# TiLDA_Mk2_Prototype_v0_1.net
KiCad netlist of a schematic drawn in EAGLE
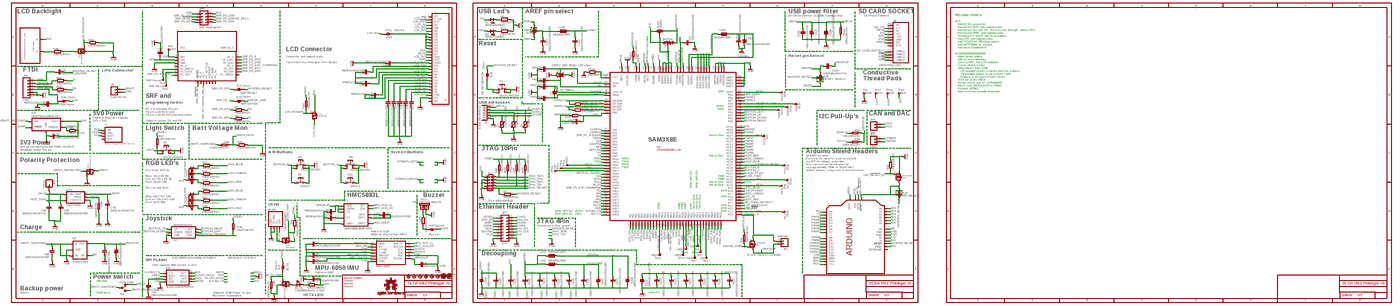
[diagram p0: schematic, sheet 1, overview]
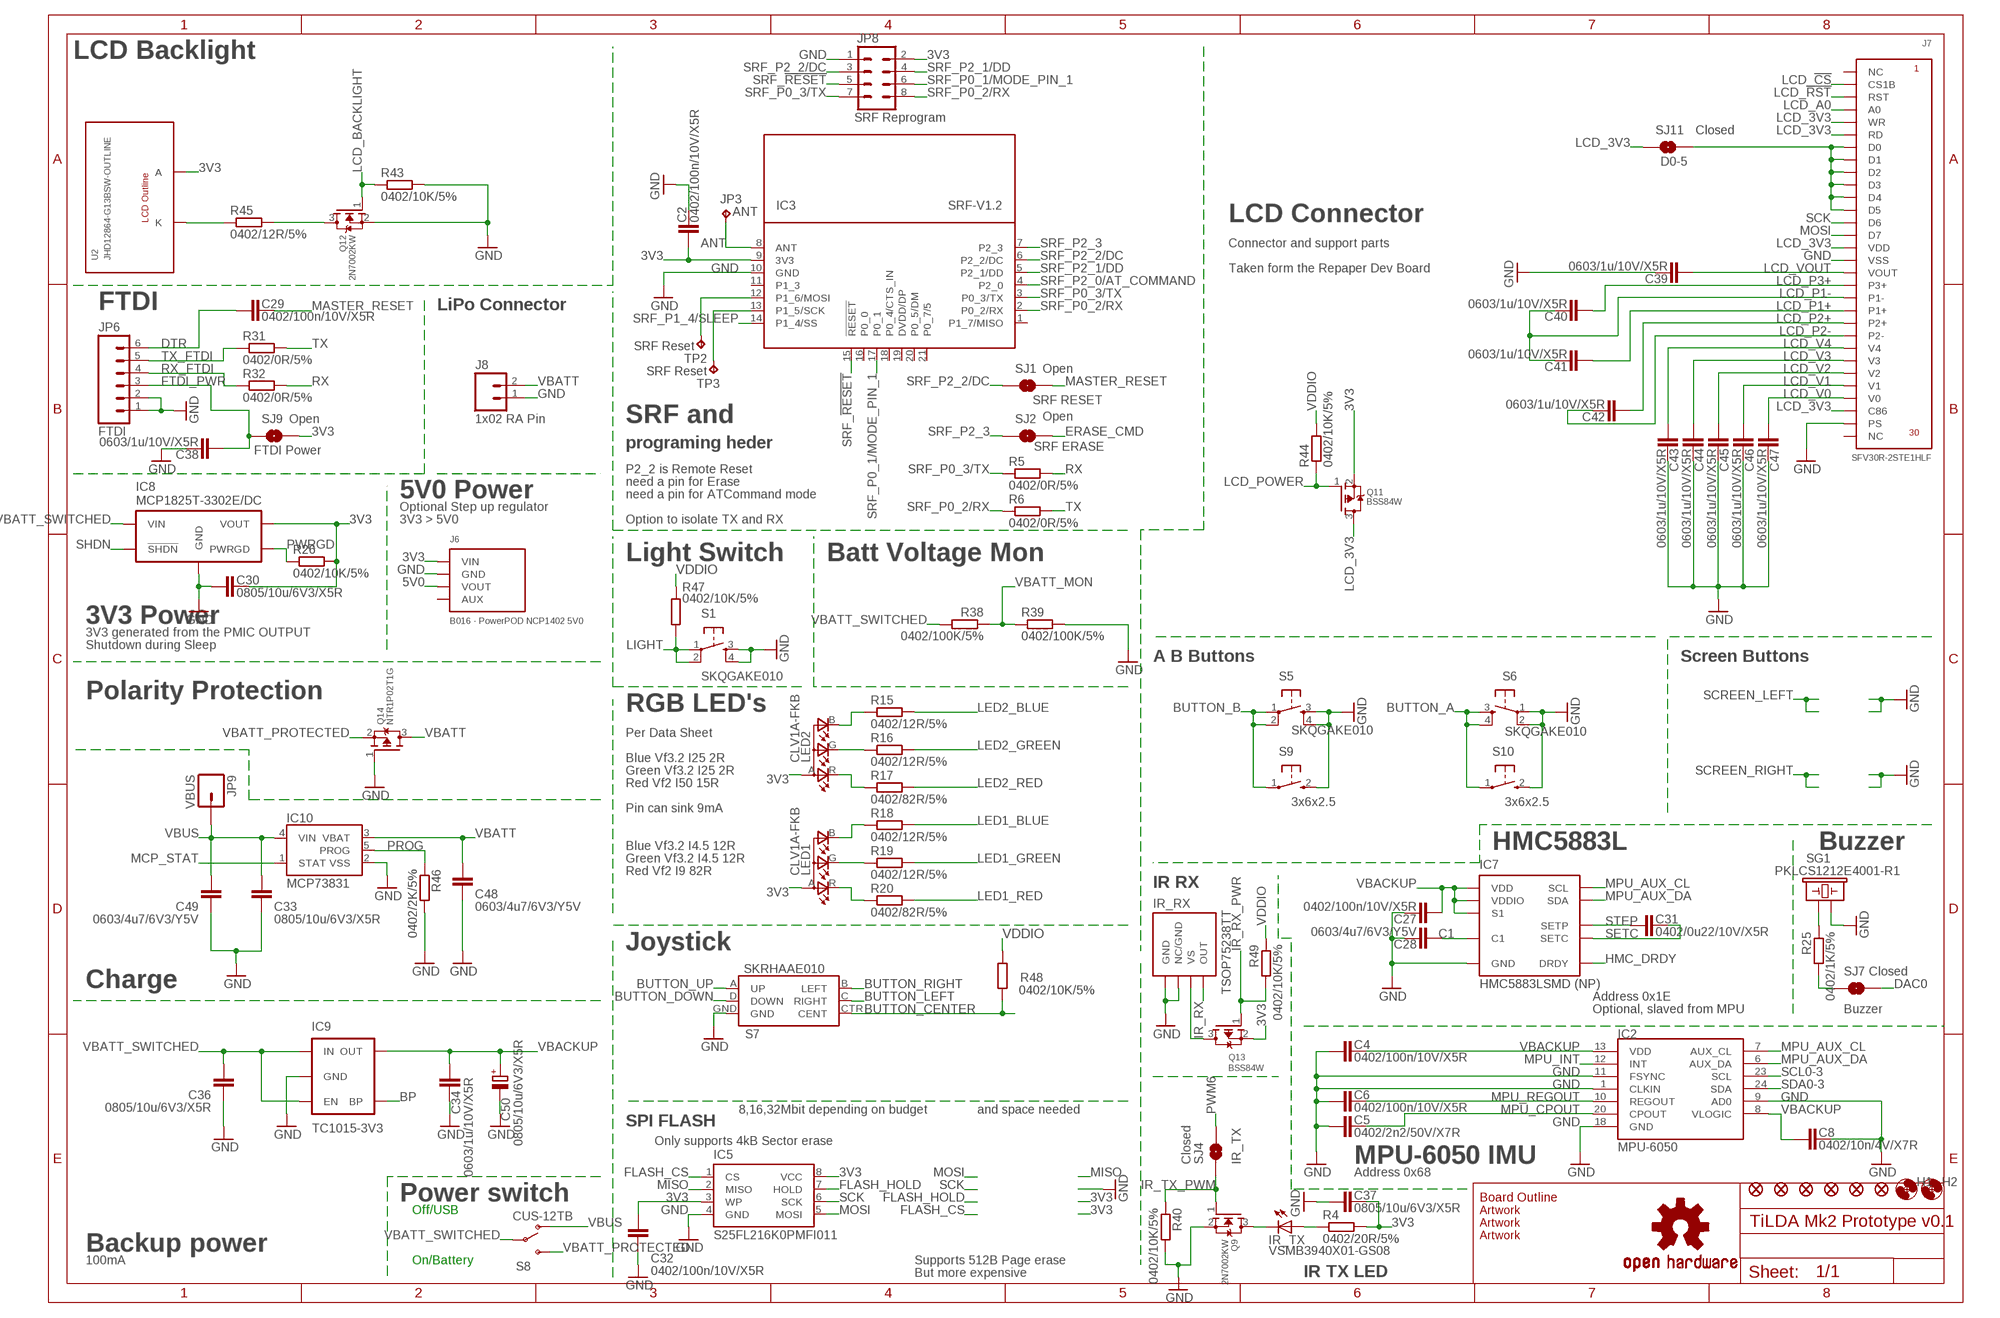
[diagram p1: schematic, sheet 1, part 1 of 4]
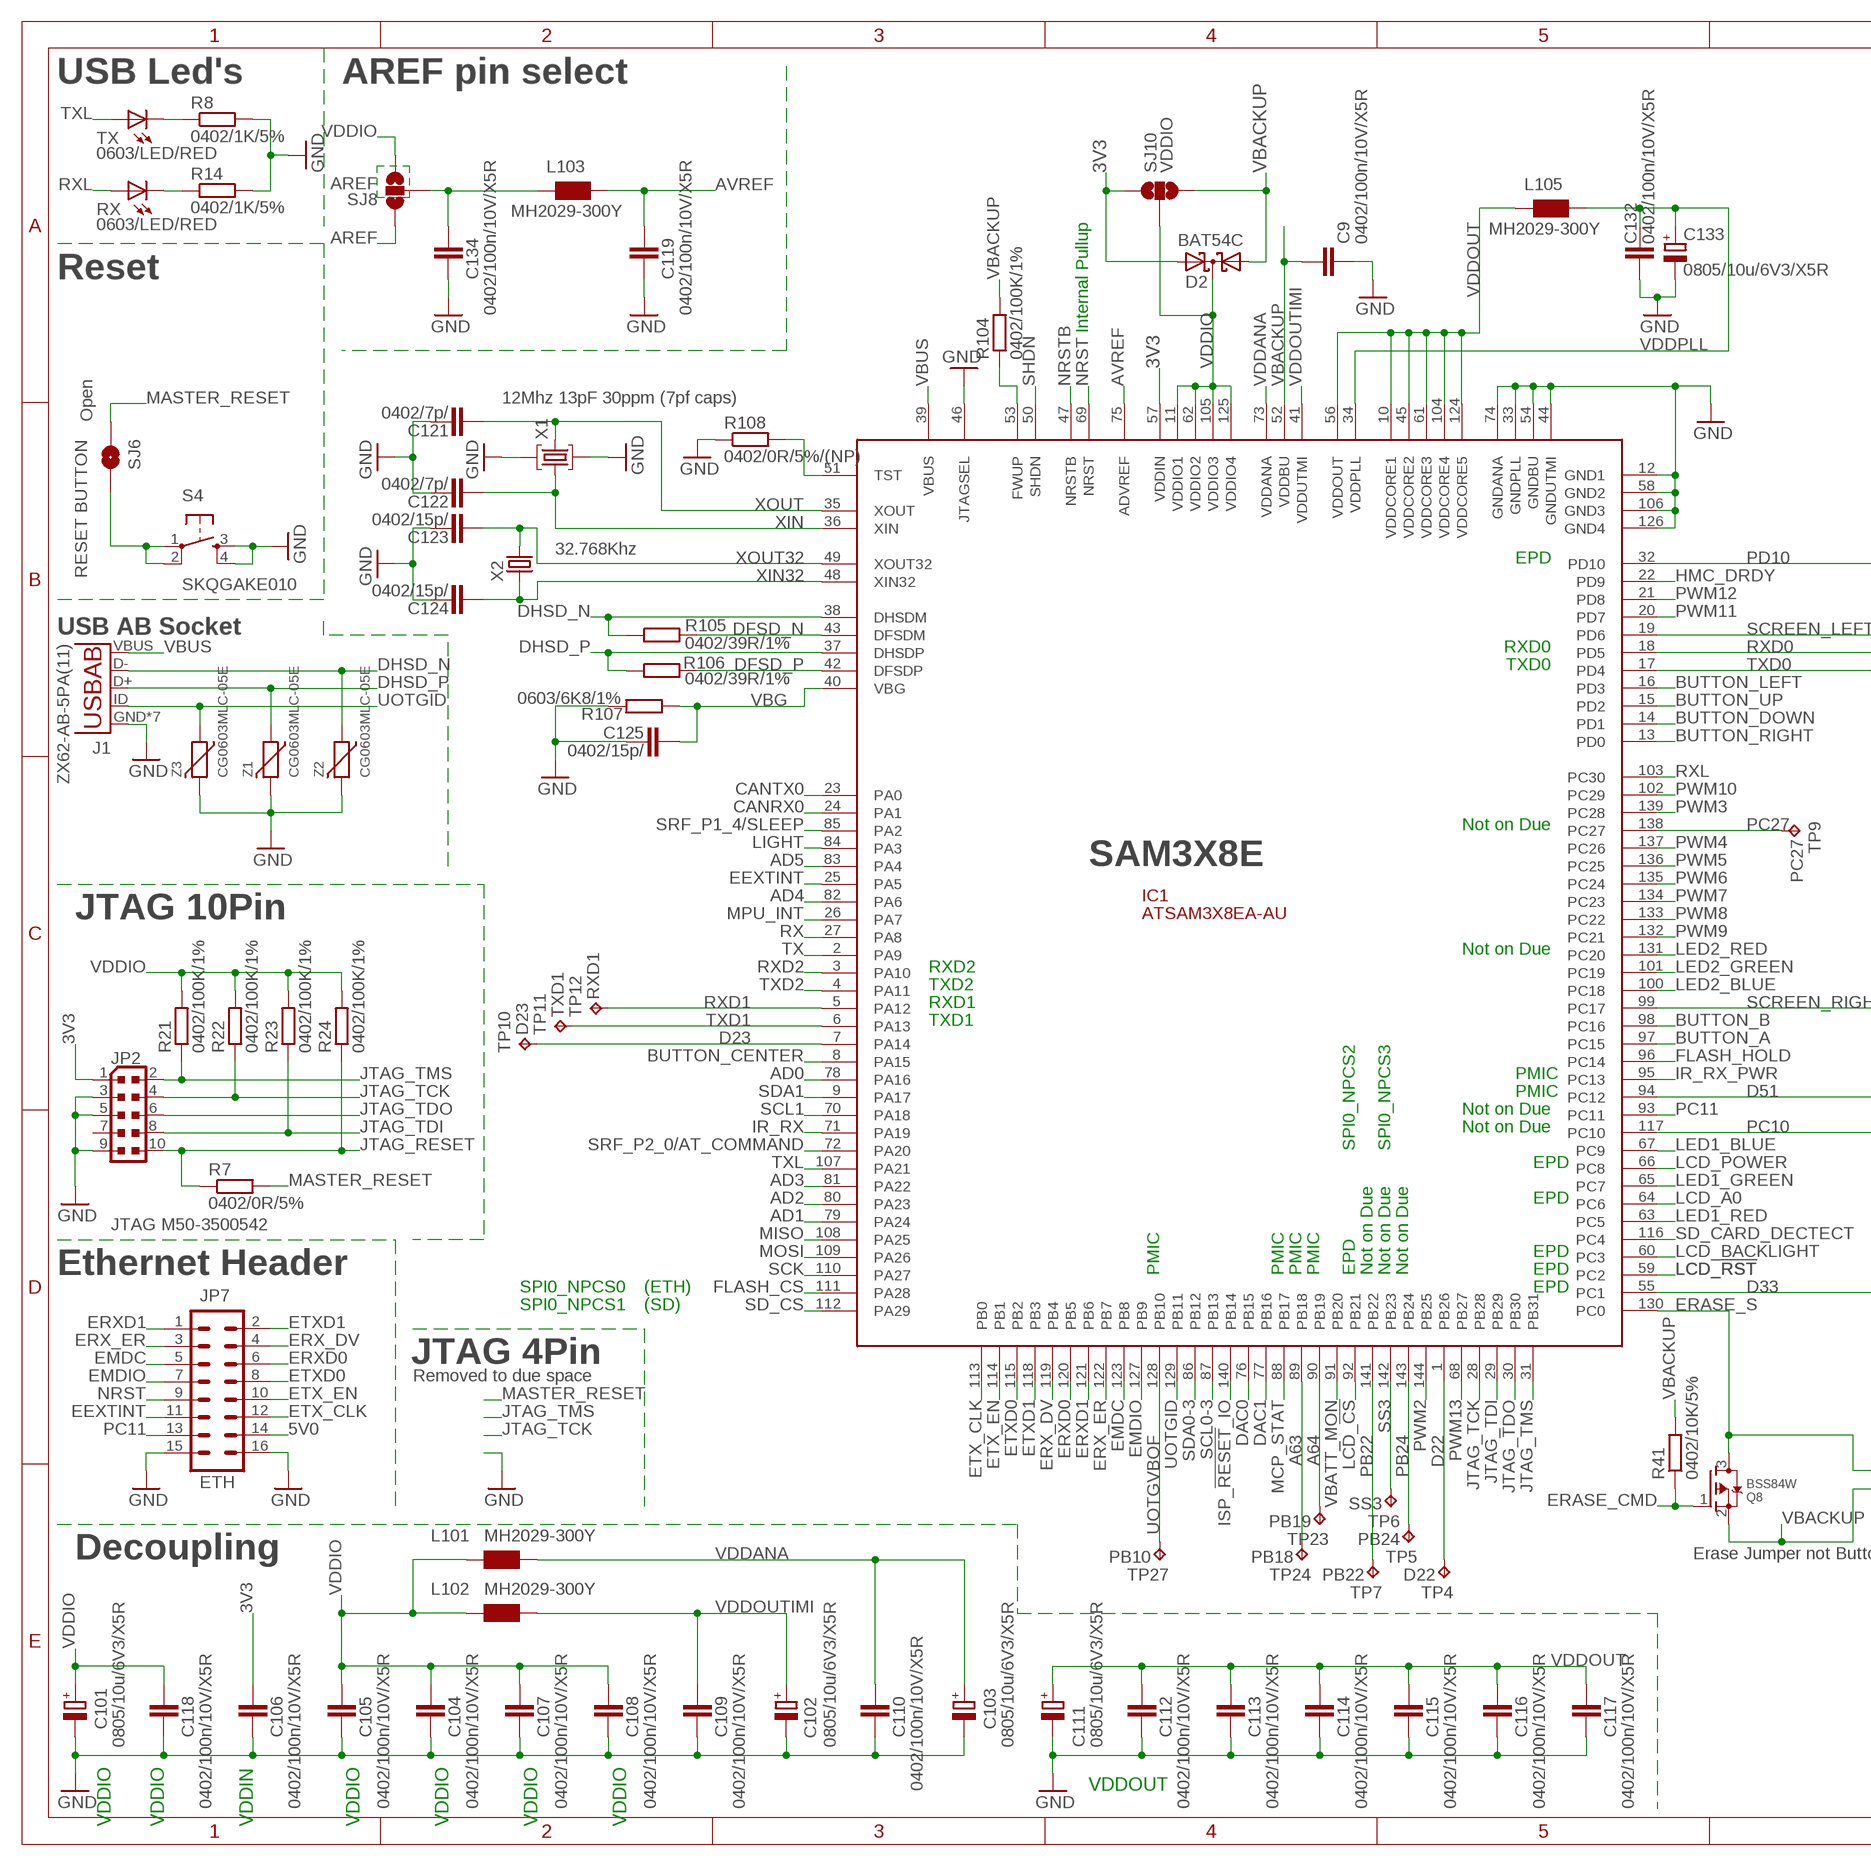
[diagram p2: schematic, sheet 1, part 2 of 4]
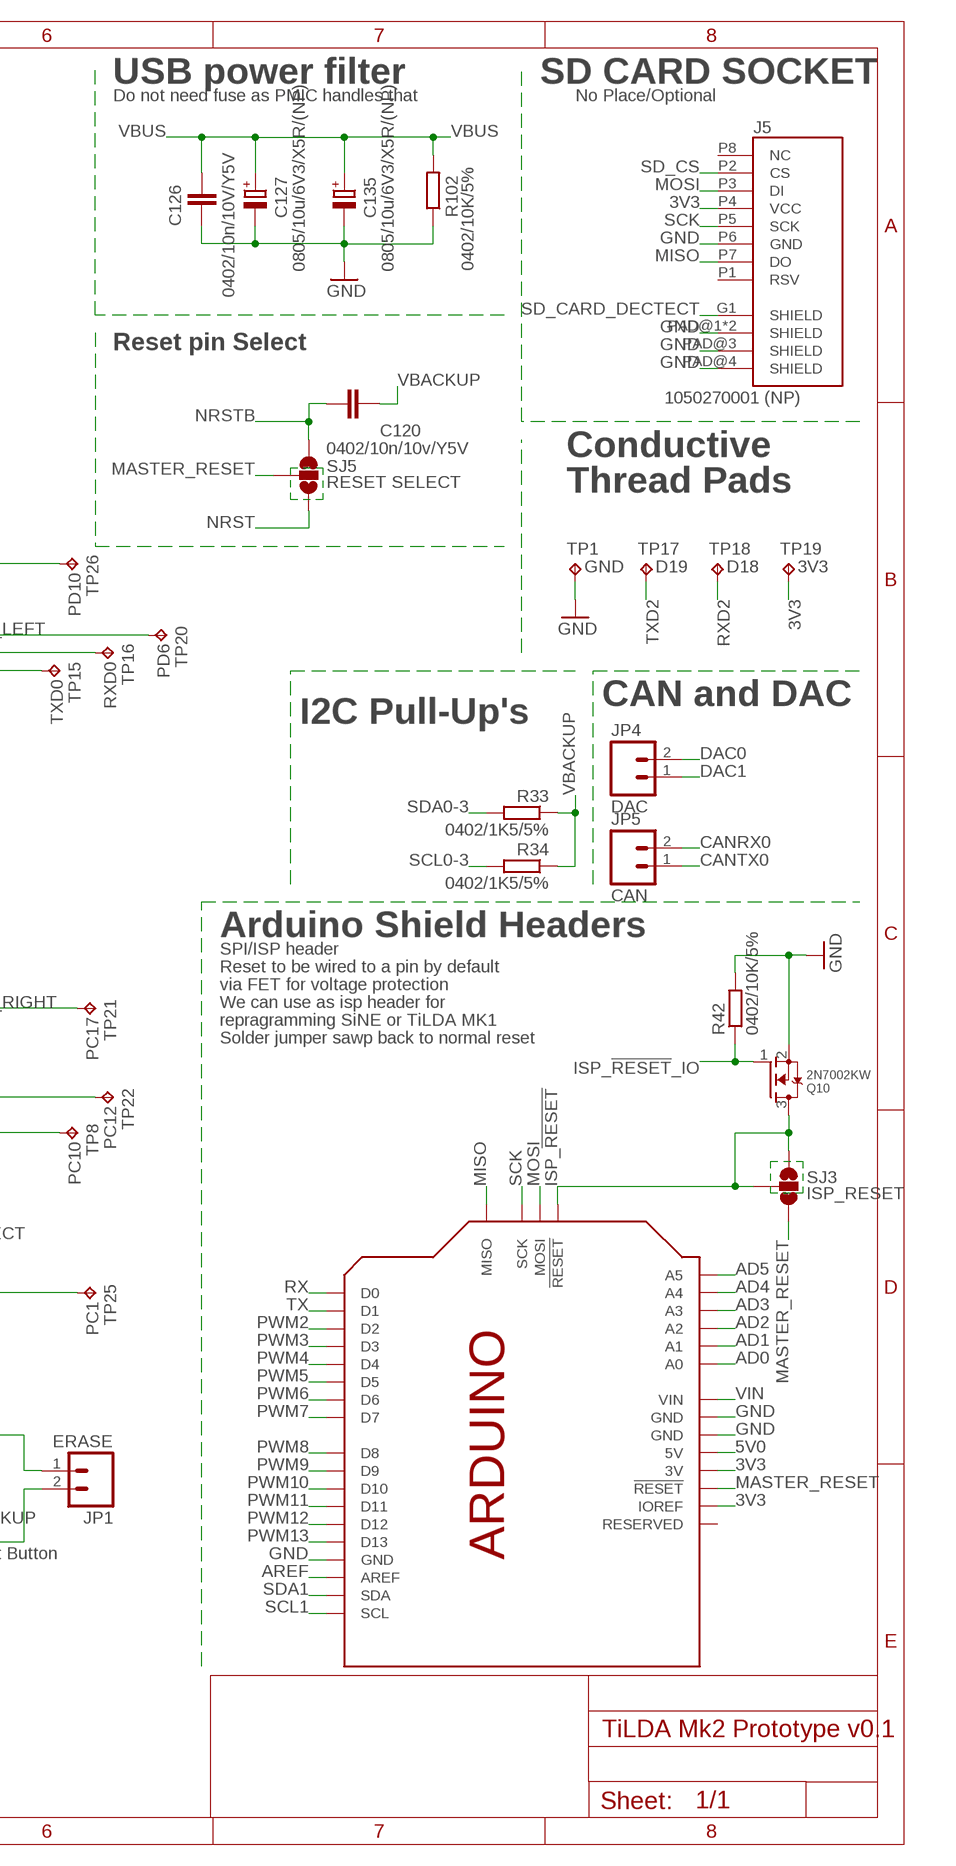
[diagram p3: schematic, sheet 1, part 3 of 4]
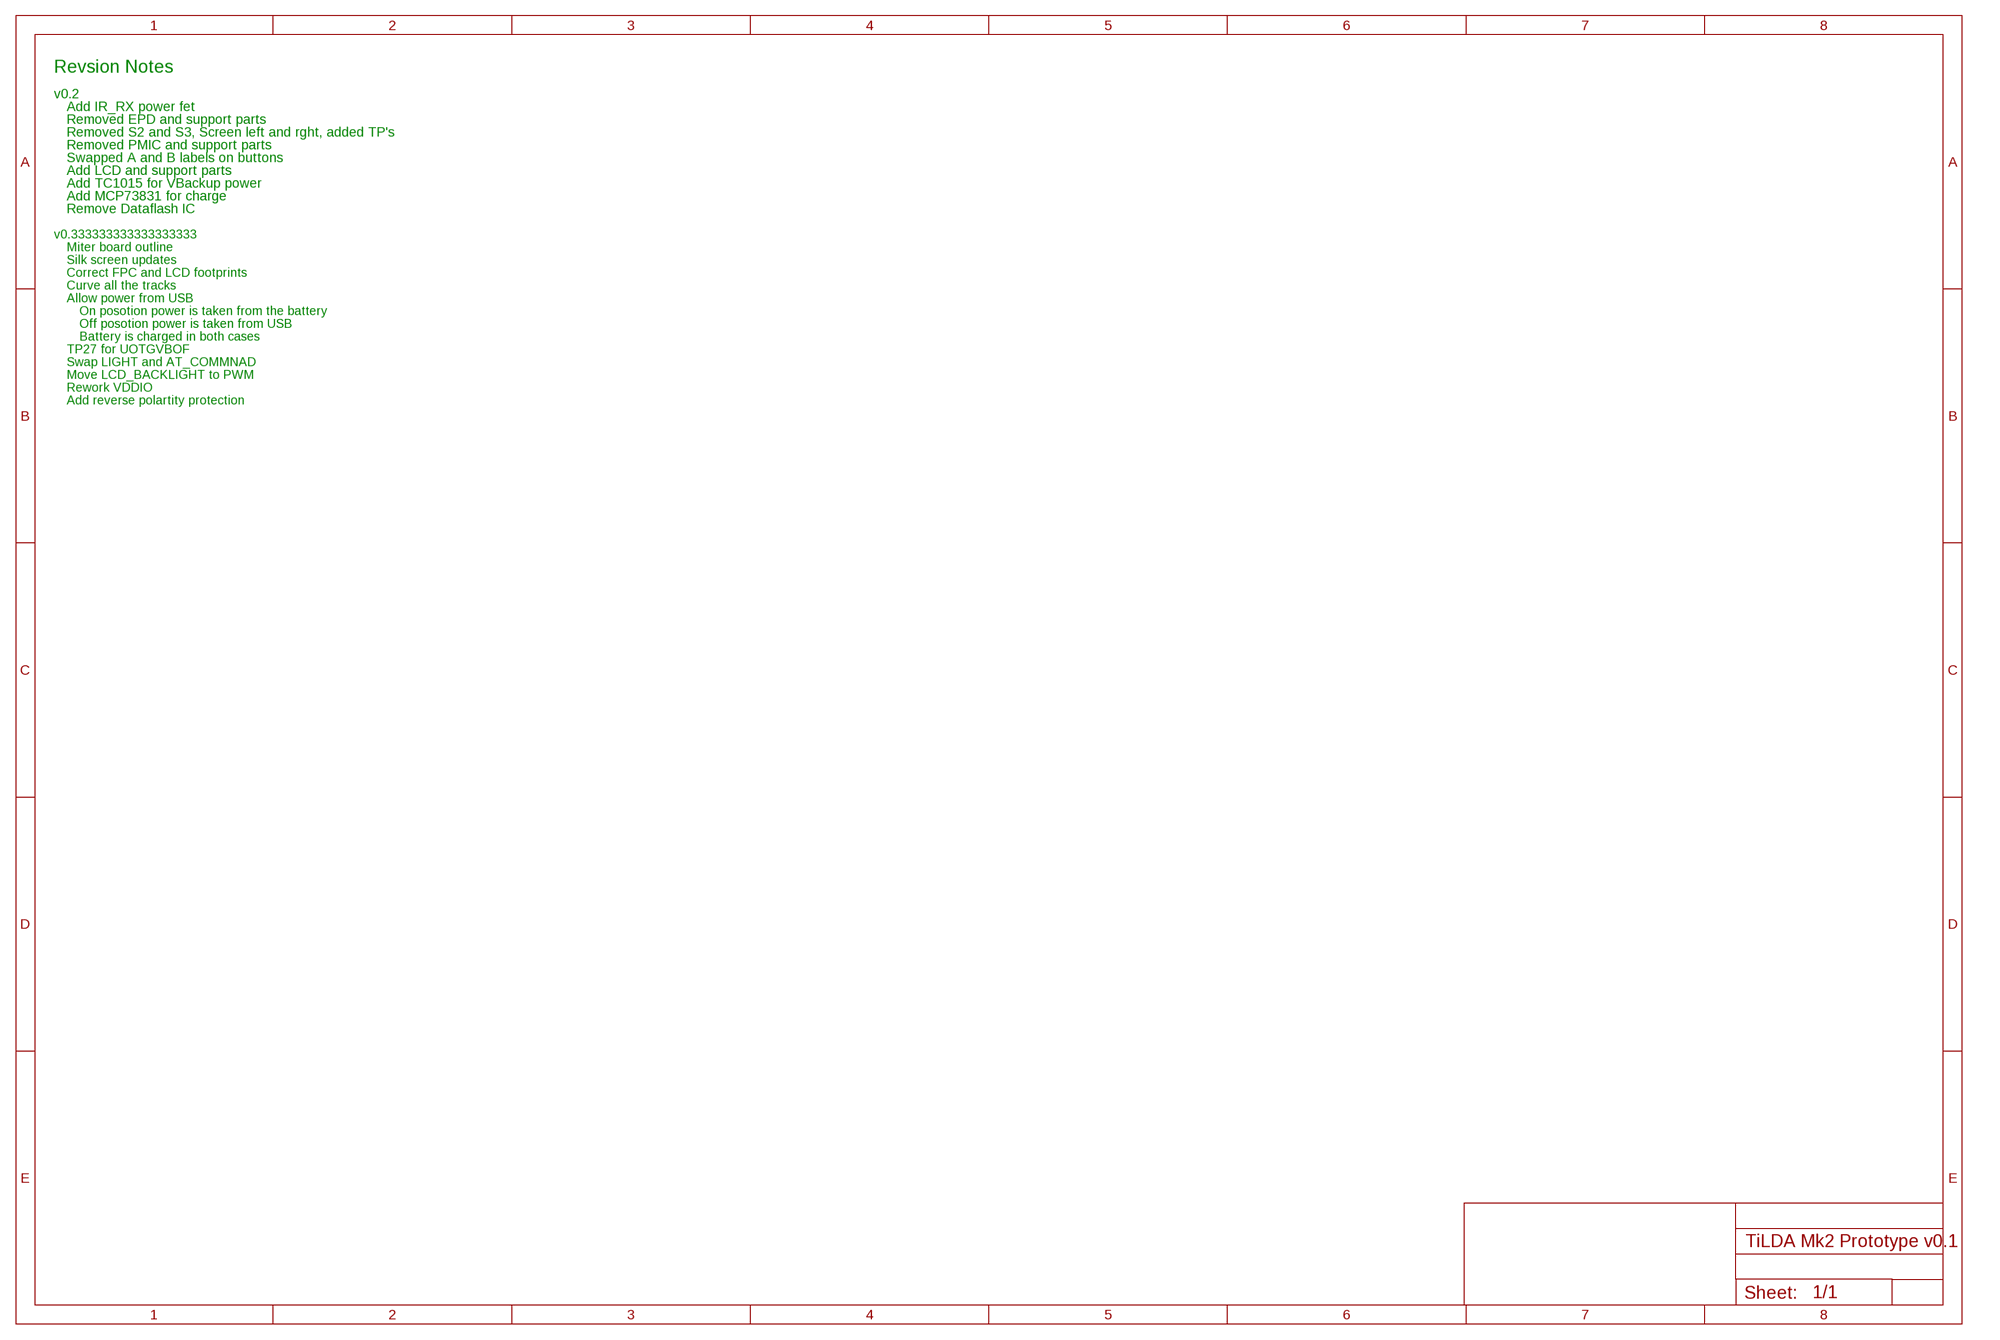
[diagram p4: schematic, sheet 1, part 4 of 4]

(export (version "E")
  (design (tool "Eeschema 10.0.6"))
  (components
    (comp (ref "ARTWORK1")
      (value "ARTWORK_FRONT1")
      (footprint "eagle-import:TILDA_ARTWORK_FRONT1")
      (libsource (lib "eagle-import") (part "ARTWORK_FRONT1"))
    )
    (comp (ref "ARTWORK2")
      (value "ARTWORK_ACHIEVEMENT2")
      (footprint "eagle-import:TILDA_ARTWORK_ACHIEVEMENT2")
      (libsource (lib "eagle-import") (part "ARTWORK_ACHIEVEMENT2"))
    )
    (comp (ref "ARTWORK3")
      (value "ARTWORK_ACHIEVEMENT3")
      (footprint "eagle-import:TILDA_ARTWORK_ACHIEVEMENT3")
      (libsource (lib "eagle-import") (part "ARTWORK_ACHIEVEMENT3"))
    )
    (comp (ref "C2")
      (value "0402/100n/10V/X5R")
      (footprint "eagle-import:C0402-ARDUINO-ROUND")
      (libsource (lib "eagle-import") (part "C-EUC0402-ARDUINO-ROUND"))
    )
    (comp (ref "C4")
      (value "0402/100n/10V/X5R")
      (footprint "eagle-import:C0402-ARDUINO-ROUND")
      (libsource (lib "eagle-import") (part "C-EUC0402-ARDUINO-ROUND"))
    )
    (comp (ref "C5")
      (value "0402/2n2/50V/X7R")
      (footprint "eagle-import:C0402-ARDUINO-ROUND")
      (libsource (lib "eagle-import") (part "C-EUC0402-ARDUINO-ROUND"))
    )
    (comp (ref "C6")
      (value "0402/100n/10V/X5R")
      (footprint "eagle-import:C0402-ARDUINO-ROUND")
      (libsource (lib "eagle-import") (part "C-EUC0402-ARDUINO-ROUND"))
    )
    (comp (ref "C8")
      (value "0402/10n/4V/X7R")
      (footprint "eagle-import:C0402-ARDUINO-ROUND")
      (libsource (lib "eagle-import") (part "C-EUC0402-ARDUINO-ROUND"))
    )
    (comp (ref "C9")
      (value "0402/100n/10V/X5R")
      (footprint "eagle-import:C0402-ARDUINO-ROUND")
      (libsource (lib "eagle-import") (part "C-EUC0402-ARDUINO-ROUND"))
    )
    (comp (ref "C27")
      (value "0402/100n/10V/X5R")
      (footprint "eagle-import:C0402-ARDUINO-ROUND")
      (libsource (lib "eagle-import") (part "C-EUC0402-ARDUINO-ROUND"))
    )
    (comp (ref "C28")
      (value "0603/4u7/6V3/Y5V")
      (footprint "eagle-import:C0603-ROUND")
      (libsource (lib "eagle-import") (part "C-EUC0603-ROUND"))
    )
    (comp (ref "C29")
      (value "0402/100n/10V/X5R")
      (footprint "eagle-import:C0402-ARDUINO-ROUND")
      (libsource (lib "eagle-import") (part "C-EUC0402-ARDUINO-ROUND"))
    )
    (comp (ref "C30")
      (value "0805/10u/6V3/X5R")
      (footprint "eagle-import:C0805RND")
      (libsource (lib "eagle-import") (part "C-EUC0805RND"))
    )
    (comp (ref "C31")
      (value "0402/0u22/10V/X5R")
      (footprint "eagle-import:C0402-ARDUINO-ROUND")
      (libsource (lib "eagle-import") (part "C-EUC0402-ARDUINO-ROUND"))
    )
    (comp (ref "C32")
      (value "0402/100n/10V/X5R")
      (footprint "eagle-import:C0402-ARDUINO-ROUND")
      (libsource (lib "eagle-import") (part "C-EUC0402-ARDUINO-ROUND"))
    )
    (comp (ref "C33")
      (value "0805/10u/6V3/X5R")
      (footprint "eagle-import:C0805RND")
      (libsource (lib "eagle-import") (part "C-EUC0805RND"))
    )
    (comp (ref "C34")
      (value "0603/1u/10V/X5R")
      (footprint "eagle-import:C0603-ROUND")
      (libsource (lib "eagle-import") (part "C-EUC0603-ROUND"))
    )
    (comp (ref "C36")
      (value "0805/10u/6V3/X5R")
      (footprint "eagle-import:C0805RND")
      (libsource (lib "eagle-import") (part "C-EUC0805RND"))
    )
    (comp (ref "C37")
      (value "0805/10u/6V3/X5R")
      (footprint "eagle-import:C0805RND")
      (libsource (lib "eagle-import") (part "C-EUC0805RND"))
    )
    (comp (ref "C38")
      (value "0603/1u/10V/X5R")
      (footprint "eagle-import:C0603-ROUND")
      (libsource (lib "eagle-import") (part "C-EUC0603-ROUND"))
    )
    (comp (ref "C39")
      (value "0603/1u/10V/X5R")
      (footprint "eagle-import:C0603-ROUND")
      (libsource (lib "eagle-import") (part "C-EUC0603-ROUND"))
    )
    (comp (ref "C40")
      (value "0603/1u/10V/X5R")
      (footprint "eagle-import:C0603-ROUND")
      (libsource (lib "eagle-import") (part "C-EUC0603-ROUND"))
    )
    (comp (ref "C41")
      (value "0603/1u/10V/X5R")
      (footprint "eagle-import:C0603-ROUND")
      (libsource (lib "eagle-import") (part "C-EUC0603-ROUND"))
    )
    (comp (ref "C42")
      (value "0603/1u/10V/X5R")
      (footprint "eagle-import:C0603-ROUND")
      (libsource (lib "eagle-import") (part "C-EUC0603-ROUND"))
    )
    (comp (ref "C43")
      (value "0603/1u/10V/X5R")
      (footprint "eagle-import:C0603-ROUND")
      (libsource (lib "eagle-import") (part "C-EUC0603-ROUND"))
    )
    (comp (ref "C44")
      (value "0603/1u/10V/X5R")
      (footprint "eagle-import:C0603-ROUND")
      (libsource (lib "eagle-import") (part "C-EUC0603-ROUND"))
    )
    (comp (ref "C45")
      (value "0603/1u/10V/X5R")
      (footprint "eagle-import:C0603-ROUND")
      (libsource (lib "eagle-import") (part "C-EUC0603-ROUND"))
    )
    (comp (ref "C46")
      (value "0603/1u/10V/X5R")
      (footprint "eagle-import:C0603-ROUND")
      (libsource (lib "eagle-import") (part "C-EUC0603-ROUND"))
    )
    (comp (ref "C47")
      (value "0603/1u/10V/X5R")
      (footprint "eagle-import:C0603-ROUND")
      (libsource (lib "eagle-import") (part "C-EUC0603-ROUND"))
    )
    (comp (ref "C48")
      (value "0603/4u7/6V3/Y5V")
      (footprint "eagle-import:C0603-ROUND")
      (libsource (lib "eagle-import") (part "C-EUC0603-ROUND"))
    )
    (comp (ref "C49")
      (value "0603/4u7/6V3/Y5V")
      (footprint "eagle-import:C0603-ROUND")
      (libsource (lib "eagle-import") (part "C-EUC0603-ROUND"))
    )
    (comp (ref "C50")
      (value "0805/10u/6V3/X5R")
      (footprint "eagle-import:C0805RNDPOL")
      (libsource (lib "eagle-import") (part "CPOL-EU-C0805RNDPOL"))
    )
    (comp (ref "C101")
      (value "0805/10u/6V3/X5R")
      (footprint "eagle-import:C0805RNDPOL")
      (libsource (lib "eagle-import") (part "CPOL-EU-C0805RNDPOL"))
    )
    (comp (ref "C102")
      (value "0805/10u/6V3/X5R")
      (footprint "eagle-import:C0805RNDPOL")
      (libsource (lib "eagle-import") (part "CPOL-EU-C0805RNDPOL"))
    )
    (comp (ref "C103")
      (value "0805/10u/6V3/X5R")
      (footprint "eagle-import:C0805RNDPOL")
      (libsource (lib "eagle-import") (part "CPOL-EU-C0805RNDPOL"))
    )
    (comp (ref "C104")
      (value "0402/100n/10V/X5R")
      (footprint "eagle-import:C0402-ARDUINO-ROUND")
      (libsource (lib "eagle-import") (part "C-EUC0402-ARDUINO-ROUND"))
    )
    (comp (ref "C105")
      (value "0402/100n/10V/X5R")
      (footprint "eagle-import:C0402-ARDUINO-ROUND")
      (libsource (lib "eagle-import") (part "C-EUC0402-ARDUINO-ROUND"))
    )
    (comp (ref "C106")
      (value "0402/100n/10V/X5R")
      (footprint "eagle-import:C0402-ARDUINO-ROUND")
      (libsource (lib "eagle-import") (part "C-EUC0402-ARDUINO-ROUND"))
    )
    (comp (ref "C107")
      (value "0402/100n/10V/X5R")
      (footprint "eagle-import:C0402-ARDUINO-ROUND")
      (libsource (lib "eagle-import") (part "C-EUC0402-ARDUINO-ROUND"))
    )
    (comp (ref "C108")
      (value "0402/100n/10V/X5R")
      (footprint "eagle-import:C0402-ARDUINO-ROUND")
      (libsource (lib "eagle-import") (part "C-EUC0402-ARDUINO-ROUND"))
    )
    (comp (ref "C109")
      (value "0402/100n/10V/X5R")
      (footprint "eagle-import:C0402-ARDUINO-ROUND")
      (libsource (lib "eagle-import") (part "C-EUC0402-ARDUINO-ROUND"))
    )
    (comp (ref "C110")
      (value "0402/100n/10V/X5R")
      (footprint "eagle-import:C0402-ARDUINO-ROUND")
      (libsource (lib "eagle-import") (part "C-EUC0402-ARDUINO-ROUND"))
    )
    (comp (ref "C111")
      (value "0805/10u/6V3/X5R")
      (footprint "eagle-import:C0805RNDPOL")
      (libsource (lib "eagle-import") (part "CPOL-EU-C0805RNDPOL"))
    )
    (comp (ref "C112")
      (value "0402/100n/10V/X5R")
      (footprint "eagle-import:C0402-ARDUINO-ROUND")
      (libsource (lib "eagle-import") (part "C-EUC0402-ARDUINO-ROUND"))
    )
    (comp (ref "C113")
      (value "0402/100n/10V/X5R")
      (footprint "eagle-import:C0402-ARDUINO-ROUND")
      (libsource (lib "eagle-import") (part "C-EUC0402-ARDUINO-ROUND"))
    )
    (comp (ref "C114")
      (value "0402/100n/10V/X5R")
      (footprint "eagle-import:C0402-ARDUINO-ROUND")
      (libsource (lib "eagle-import") (part "C-EUC0402-ARDUINO-ROUND"))
    )
    (comp (ref "C115")
      (value "0402/100n/10V/X5R")
      (footprint "eagle-import:C0402-ARDUINO-ROUND")
      (libsource (lib "eagle-import") (part "C-EUC0402-ARDUINO-ROUND"))
    )
    (comp (ref "C116")
      (value "0402/100n/10V/X5R")
      (footprint "eagle-import:C0402-ARDUINO-ROUND")
      (libsource (lib "eagle-import") (part "C-EUC0402-ARDUINO-ROUND"))
    )
    (comp (ref "C117")
      (value "0402/100n/10V/X5R")
      (footprint "eagle-import:C0402-ARDUINO-ROUND")
      (libsource (lib "eagle-import") (part "C-EUC0402-ARDUINO-ROUND"))
    )
    (comp (ref "C118")
      (value "0402/100n/10V/X5R")
      (footprint "eagle-import:C0402-ARDUINO-ROUND")
      (libsource (lib "eagle-import") (part "C-EUC0402-ARDUINO-ROUND"))
    )
    (comp (ref "C119")
      (value "0402/100n/10V/X5R")
      (footprint "eagle-import:C0402-ARDUINO-ROUND")
      (libsource (lib "eagle-import") (part "C-EUC0402-ARDUINO-ROUND"))
    )
    (comp (ref "C120")
      (value "0402/10n/10v/Y5V")
      (footprint "eagle-import:C0402-ARDUINO-ROUND")
      (libsource (lib "eagle-import") (part "C-EUC0402-ARDUINO-ROUND"))
    )
    (comp (ref "C121")
      (value "0402/7p/")
      (footprint "eagle-import:C0402-ARDUINO-ROUND")
      (libsource (lib "eagle-import") (part "C-EUC0402-ARDUINO-ROUND"))
    )
    (comp (ref "C122")
      (value "0402/7p/")
      (footprint "eagle-import:C0402-ARDUINO-ROUND")
      (libsource (lib "eagle-import") (part "C-EUC0402-ARDUINO-ROUND"))
    )
    (comp (ref "C123")
      (value "0402/15p/")
      (footprint "eagle-import:C0402-ARDUINO-ROUND")
      (libsource (lib "eagle-import") (part "C-EUC0402-ARDUINO-ROUND"))
    )
    (comp (ref "C124")
      (value "0402/15p/")
      (footprint "eagle-import:C0402-ARDUINO-ROUND")
      (libsource (lib "eagle-import") (part "C-EUC0402-ARDUINO-ROUND"))
    )
    (comp (ref "C125")
      (value "0402/15p/")
      (footprint "eagle-import:C0402-ARDUINO-ROUND")
      (libsource (lib "eagle-import") (part "C-EUC0402-ARDUINO-ROUND"))
    )
    (comp (ref "C126")
      (value "0402/10n/10V/Y5V")
      (footprint "eagle-import:C0402-ARDUINO-ROUND")
      (libsource (lib "eagle-import") (part "C-EUC0402-ARDUINO-ROUND"))
    )
    (comp (ref "C127")
      (value "0805/10u/6V3/X5R/(NP)")
      (footprint "eagle-import:C0805RNDPOL")
      (libsource (lib "eagle-import") (part "CPOL-EU-C0805RNDPOL"))
    )
    (comp (ref "C132")
      (value "0402/100n/10V/X5R")
      (footprint "eagle-import:C0402-ARDUINO-ROUND")
      (libsource (lib "eagle-import") (part "C-EUC0402-ARDUINO-ROUND"))
    )
    (comp (ref "C133")
      (value "0805/10u/6V3/X5R")
      (footprint "eagle-import:C0805RNDPOL")
      (libsource (lib "eagle-import") (part "CPOL-EU-C0805RNDPOL"))
    )
    (comp (ref "C134")
      (value "0402/100n/10V/X5R")
      (footprint "eagle-import:C0402-ARDUINO-ROUND")
      (libsource (lib "eagle-import") (part "C-EUC0402-ARDUINO-ROUND"))
    )
    (comp (ref "C135")
      (value "0805/10u/6V3/X5R/(NP)")
      (footprint "eagle-import:C0805RNDPOL")
      (libsource (lib "eagle-import") (part "CPOL-EU-C0805RNDPOL"))
    )
    (comp (ref "D2")
      (value "BAT54C")
      (footprint "eagle-import:SOT23")
      (libsource (lib "eagle-import") (part "BAT54C"))
    )
    (comp (ref "FID1")
      (value "FIDUCIAL1X2.5-STOP")
      (footprint "eagle-import:FIDUCIAL-1X2.5-STOP")
      (libsource (lib "eagle-import") (part "FIDUCIAL1X2.5-STOP"))
    )
    (comp (ref "FID2")
      (value "FIDUCIAL1X2.5-STOP")
      (footprint "eagle-import:FIDUCIAL-1X2.5-STOP")
      (libsource (lib "eagle-import") (part "FIDUCIAL1X2.5-STOP"))
    )
    (comp (ref "FID3")
      (value "FIDUCIAL1X2.5-STOP")
      (footprint "eagle-import:FIDUCIAL-1X2.5-STOP")
      (libsource (lib "eagle-import") (part "FIDUCIAL1X2.5-STOP"))
    )
    (comp (ref "FID4")
      (value "FIDUCIAL1X2.5-STOP")
      (footprint "eagle-import:FIDUCIAL-1X2.5-STOP")
      (libsource (lib "eagle-import") (part "FIDUCIAL1X2.5-STOP"))
    )
    (comp (ref "FID5")
      (value "FIDUCIAL1X2.5-STOP")
      (footprint "eagle-import:FIDUCIAL-1X2.5-STOP")
      (libsource (lib "eagle-import") (part "FIDUCIAL1X2.5-STOP"))
    )
    (comp (ref "FID6")
      (value "FIDUCIAL1X2.5-STOP")
      (footprint "eagle-import:FIDUCIAL-1X2.5-STOP")
      (libsource (lib "eagle-import") (part "FIDUCIAL1X2.5-STOP"))
    )
    (comp (ref "H1")
      (value "MOUNT-HOLE4.5-LWK")
      (footprint "eagle-import:4,5-LWK")
      (libsource (lib "eagle-import") (part "MOUNT-HOLE4.5-LWK"))
    )
    (comp (ref "H2")
      (value "MOUNT-HOLE4.5-LWK")
      (footprint "eagle-import:4,5-LWK")
      (libsource (lib "eagle-import") (part "MOUNT-HOLE4.5-LWK"))
    )
    (comp (ref "IC1")
      (value "ATSAM3X8EA-AU")
      (footprint "eagle-import:LQFP144")
      (libsource (lib "eagle-import") (part "ATSAM3X/AAU"))
    )
    (comp (ref "IC2")
      (value "MPU-6050")
      (footprint "eagle-import:QFN-24-NODIE")
      (libsource (lib "eagle-import") (part "MPU-6050"))
    )
    (comp (ref "IC3")
      (value "SRF-V1.2")
      (footprint "eagle-import:SRF-LANDING-1.2")
      (libsource (lib "eagle-import") (part "SRF-LANDING-1.2"))
    )
    (comp (ref "IC5")
      (value "S25FL216K0PMFI011")
      (footprint "eagle-import:SO08-EIAJ")
      (libsource (lib "eagle-import") (part "SPI_FLASH-X25XXSMD1"))
    )
    (comp (ref "IC7")
      (value "HMC5883LSMD (NP)")
      (footprint "eagle-import:16LPCC")
      (libsource (lib "eagle-import") (part "HMC5883LSMD"))
    )
    (comp (ref "IC8")
      (value "MCP1825T-3302E/DC")
      (footprint "eagle-import:SOT127P700X180-6N")
      (libsource (lib "eagle-import") (part "MCP1825T-3302E/DC"))
    )
    (comp (ref "IC9")
      (value "TC1015-3V3")
      (footprint "eagle-import:SOT23-5")
      (libsource (lib "eagle-import") (part "V_REG_LDOSMD"))
    )
    (comp (ref "IC10")
      (value "MCP73831")
      (footprint "eagle-import:SOT23-5")
      (libsource (lib "eagle-import") (part "MCP73831"))
    )
    (comp (ref "IR_RX")
      (value "TSOP75238TT")
      (footprint "eagle-import:TSOP75X")
      (libsource (lib "eagle-import") (part "IR-RECEIVERTSOP75438TT"))
    )
    (comp (ref "IR_TX")
      (value "VSMB3940X01-GS08")
      (footprint "eagle-import:P-LCC-2")
      (libsource (lib "eagle-import") (part "IR-SENDER-PLCC"))
    )
    (comp (ref "J1")
      (value "ZX62-AB-5PA(11)")
      (footprint "eagle-import:USB-AB-MICRO-SMD_LWK")
      (libsource (lib "eagle-import") (part "USB-AB-LWK"))
    )
    (comp (ref "J3")
      (value "Arduino Headers")
      (footprint "eagle-import:ARDUINOR3-LWKTXT-REF-SPI")
      (libsource (lib "eagle-import") (part "ARDUINOSPI-REFRENCE"))
    )
    (comp (ref "J5")
      (value "1050270001 (NP)")
      (footprint "eagle-import:105027-LWK")
      (libsource (lib "eagle-import") (part "USD-SOCKET-105027-LWK"))
    )
    (comp (ref "J6")
      (value "B016 - PowerPOD NCP1402 5V0")
      (footprint "eagle-import:POWER-POD-EMF")
      (libsource (lib "eagle-import") (part "POWER-POD-EMF"))
    )
    (comp (ref "J7")
      (value "SFV30R-2STE1HLF")
      (footprint "eagle-import:SFV30R-2STE1HLF")
      (libsource (lib "eagle-import") (part "JHD12863-G13BSW-CONNECTOR-SFV30R-2STE1HLF"))
    )
    (comp (ref "J8")
      (value "1x02 RA Pin")
      (footprint "eagle-import:1X02_RA")
      (libsource (lib "eagle-import") (part "M02RA"))
    )
    (comp (ref "JP1")
      (value "ERASE")
      (footprint "eagle-import:1X02")
      (libsource (lib "eagle-import") (part "M02PTH"))
    )
    (comp (ref "JP2")
      (value "JTAG M50-3500542")
      (footprint "eagle-import:PINHEAD_2X05_127")
      (libsource (lib "eagle-import") (part "PINHEAD_PINHD-2X5PASSO127"))
    )
    (comp (ref "JP3")
      (value "ANT")
      (footprint "eagle-import:P1-13")
      (libsource (lib "eagle-import") (part "TPPAD1-13"))
    )
    (comp (ref "JP4")
      (value "DAC")
      (footprint "eagle-import:1X02_NO_SILK_OCT")
      (libsource (lib "eagle-import") (part "M021X02_NO_SILK_OCT"))
    )
    (comp (ref "JP5")
      (value "CAN")
      (footprint "eagle-import:1X02_NO_SILK_OCT")
      (libsource (lib "eagle-import") (part "M021X02_NO_SILK_OCT"))
    )
    (comp (ref "JP6")
      (value "FTDI")
      (footprint "eagle-import:1X06")
      (libsource (lib "eagle-import") (part "M06SIP"))
    )
    (comp (ref "JP7")
      (value "ETH")
      (footprint "eagle-import:2X8")
      (libsource (lib "eagle-import") (part "M08X2"))
    )
    (comp (ref "JP8")
      (value "SRF Reprogram")
      (footprint "eagle-import:2X4-PAD")
      (libsource (lib "eagle-import") (part "M04X2-PAD"))
    )
    (comp (ref "JP9")
      (value "VBUS")
      (footprint "eagle-import:1X01")
      (libsource (lib "eagle-import") (part "M01PTH"))
    )
    (comp (ref "L101")
      (value "MH2029-300Y")
      (footprint "eagle-import:WUERTH-0805")
      (libsource (lib "eagle-import") (part "WE-CBF_0805"))
    )
    (comp (ref "L102")
      (value "MH2029-300Y")
      (footprint "eagle-import:WUERTH-0805")
      (libsource (lib "eagle-import") (part "WE-CBF_0805"))
    )
    (comp (ref "L103")
      (value "MH2029-300Y")
      (footprint "eagle-import:WUERTH-0805")
      (libsource (lib "eagle-import") (part "WE-CBF_0805"))
    )
    (comp (ref "L105")
      (value "MH2029-300Y")
      (footprint "eagle-import:WUERTH-0805")
      (libsource (lib "eagle-import") (part "WE-CBF_0805"))
    )
    (comp (ref "LED1")
      (value "CLV1A-FKB")
      (footprint "eagle-import:LED-RGB_CLV1A-FKB")
      (libsource (lib "eagle-import") (part "LED-RGB_CLV1A-FKB"))
    )
    (comp (ref "LED2")
      (value "CLV1A-FKB")
      (footprint "eagle-import:LED-RGB_CLV1A-FKB")
      (libsource (lib "eagle-import") (part "LED-RGB_CLV1A-FKB"))
    )
    (comp (ref "LOGO1")
      (value "OSHW-LOGOM")
      (footprint "eagle-import:OSHW-LOGO-M")
      (libsource (lib "eagle-import") (part "OSHW-LOGOM"))
    )
    (comp (ref "OUTLINE1")
      (value "TILDA_BOARDOUTLINE-MITER")
      (footprint "eagle-import:TILDA_BADGEBOARDBARE-VERYWIDE-MITER")
      (libsource (lib "eagle-import") (part "TILDA_BOARDOUTLINE-MITER"))
    )
    (comp (ref "Q8")
      (value "BSS84W")
      (footprint "eagle-import:SC70-3-R")
      (libsource (lib "eagle-import") (part "MOSFET-P-SC70-3"))
    )
    (comp (ref "Q9")
      (value "2N7002KW")
      (footprint "eagle-import:SC70-3-R")
      (libsource (lib "eagle-import") (part "MOSFET-NSC70-3"))
    )
    (comp (ref "Q10")
      (value "2N7002KW")
      (footprint "eagle-import:SC70-3-R")
      (libsource (lib "eagle-import") (part "MOSFET-NSC70-3"))
    )
    (comp (ref "Q11")
      (value "BSS84W")
      (footprint "eagle-import:SC70-3-R")
      (libsource (lib "eagle-import") (part "MOSFET-P-SC70-3"))
    )
    (comp (ref "Q12")
      (value "2N7002KW")
      (footprint "eagle-import:SC70-3-R")
      (libsource (lib "eagle-import") (part "MOSFET-NSC70-3"))
    )
    (comp (ref "Q13")
      (value "BSS84W")
      (footprint "eagle-import:SC70-3-R")
      (libsource (lib "eagle-import") (part "MOSFET-P-SC70-3"))
    )
    (comp (ref "Q14")
      (value "NTR1P02T1G")
      (footprint "eagle-import:SOT23-R")
      (libsource (lib "eagle-import") (part "MOSFET-P-SOT23"))
    )
    (comp (ref "R4")
      (value "0402/20R/5%")
      (footprint "eagle-import:R0402-ARDUINO-ROUND")
      (libsource (lib "eagle-import") (part "R-EU_R0402-ARDUINO-ROUND"))
    )
    (comp (ref "R5")
      (value "0402/0R/5%")
      (footprint "eagle-import:R0402-ARDUINO-ROUND")
      (libsource (lib "eagle-import") (part "R-EU_R0402-ARDUINO-ROUND"))
    )
    (comp (ref "R6")
      (value "0402/0R/5%")
      (footprint "eagle-import:R0402-ARDUINO-ROUND")
      (libsource (lib "eagle-import") (part "R-EU_R0402-ARDUINO-ROUND"))
    )
    (comp (ref "R7")
      (value "0402/0R/5%")
      (footprint "eagle-import:R0402-ARDUINO-ROUND")
      (libsource (lib "eagle-import") (part "R-EU_R0402-ARDUINO-ROUND"))
    )
    (comp (ref "R8")
      (value "0402/1K/5%")
      (footprint "eagle-import:R0402-ARDUINO-ROUND")
      (libsource (lib "eagle-import") (part "R-EU_R0402-ARDUINO-ROUND"))
    )
    (comp (ref "R14")
      (value "0402/1K/5%")
      (footprint "eagle-import:R0402-ARDUINO-ROUND")
      (libsource (lib "eagle-import") (part "R-EU_R0402-ARDUINO-ROUND"))
    )
    (comp (ref "R15")
      (value "0402/12R/5%")
      (footprint "eagle-import:R0402-ARDUINO-ROUND")
      (libsource (lib "eagle-import") (part "R-EU_R0402-ARDUINO-ROUND"))
    )
    (comp (ref "R16")
      (value "0402/12R/5%")
      (footprint "eagle-import:R0402-ARDUINO-ROUND")
      (libsource (lib "eagle-import") (part "R-EU_R0402-ARDUINO-ROUND"))
    )
    (comp (ref "R17")
      (value "0402/82R/5%")
      (footprint "eagle-import:R0402-ARDUINO-ROUND")
      (libsource (lib "eagle-import") (part "R-EU_R0402-ARDUINO-ROUND"))
    )
    (comp (ref "R18")
      (value "0402/12R/5%")
      (footprint "eagle-import:R0402-ARDUINO-ROUND")
      (libsource (lib "eagle-import") (part "R-EU_R0402-ARDUINO-ROUND"))
    )
    (comp (ref "R19")
      (value "0402/12R/5%")
      (footprint "eagle-import:R0402-ARDUINO-ROUND")
      (libsource (lib "eagle-import") (part "R-EU_R0402-ARDUINO-ROUND"))
    )
    (comp (ref "R20")
      (value "0402/82R/5%")
      (footprint "eagle-import:R0402-ARDUINO-ROUND")
      (libsource (lib "eagle-import") (part "R-EU_R0402-ARDUINO-ROUND"))
    )
    (comp (ref "R21")
      (value "0402/100K/1%")
      (footprint "eagle-import:R0402-ARDUINO-ROUND")
      (libsource (lib "eagle-import") (part "R-EU_R0402-ARDUINO-ROUND"))
    )
    (comp (ref "R22")
      (value "0402/100K/1%")
      (footprint "eagle-import:R0402-ARDUINO-ROUND")
      (libsource (lib "eagle-import") (part "R-EU_R0402-ARDUINO-ROUND"))
    )
    (comp (ref "R23")
      (value "0402/100K/1%")
      (footprint "eagle-import:R0402-ARDUINO-ROUND")
      (libsource (lib "eagle-import") (part "R-EU_R0402-ARDUINO-ROUND"))
    )
    (comp (ref "R24")
      (value "0402/100K/1%")
      (footprint "eagle-import:R0402-ARDUINO-ROUND")
      (libsource (lib "eagle-import") (part "R-EU_R0402-ARDUINO-ROUND"))
    )
    (comp (ref "R25")
      (value "0402/1K/5%")
      (footprint "eagle-import:R0402-ARDUINO-ROUND")
      (libsource (lib "eagle-import") (part "R-EU_R0402-ARDUINO-ROUND"))
    )
    (comp (ref "R26")
      (value "0402/10K/5%")
      (footprint "eagle-import:R0402-ARDUINO-ROUND")
      (libsource (lib "eagle-import") (part "R-EU_R0402-ARDUINO-ROUND"))
    )
    (comp (ref "R31")
      (value "0402/0R/5%")
      (footprint "eagle-import:R0402-ARDUINO-ROUND")
      (libsource (lib "eagle-import") (part "R-EU_R0402-ARDUINO-ROUND"))
    )
    (comp (ref "R32")
      (value "0402/0R/5%")
      (footprint "eagle-import:R0402-ARDUINO-ROUND")
      (libsource (lib "eagle-import") (part "R-EU_R0402-ARDUINO-ROUND"))
    )
    (comp (ref "R33")
      (value "0402/1K5/5%")
      (footprint "eagle-import:R0402-ARDUINO-ROUND")
      (libsource (lib "eagle-import") (part "R-EU_R0402-ARDUINO-ROUND"))
    )
    (comp (ref "R34")
      (value "0402/1K5/5%")
      (footprint "eagle-import:R0402-ARDUINO-ROUND")
      (libsource (lib "eagle-import") (part "R-EU_R0402-ARDUINO-ROUND"))
    )
    (comp (ref "R38")
      (value "0402/100K/5%")
      (footprint "eagle-import:R0402-ARDUINO-ROUND")
      (libsource (lib "eagle-import") (part "R-EU_R0402-ARDUINO-ROUND"))
    )
    (comp (ref "R39")
      (value "0402/100K/5%")
      (footprint "eagle-import:R0402-ARDUINO-ROUND")
      (libsource (lib "eagle-import") (part "R-EU_R0402-ARDUINO-ROUND"))
    )
    (comp (ref "R40")
      (value "0402/10K/5%")
      (footprint "eagle-import:R0402-ARDUINO-ROUND")
      (libsource (lib "eagle-import") (part "R-EU_R0402-ARDUINO-ROUND"))
    )
    (comp (ref "R41")
      (value "0402/10K/5%")
      (footprint "eagle-import:R0402-ARDUINO-ROUND")
      (libsource (lib "eagle-import") (part "R-EU_R0402-ARDUINO-ROUND"))
    )
    (comp (ref "R42")
      (value "0402/10K/5%")
      (footprint "eagle-import:R0402-ARDUINO-ROUND")
      (libsource (lib "eagle-import") (part "R-EU_R0402-ARDUINO-ROUND"))
    )
    (comp (ref "R43")
      (value "0402/10K/5%")
      (footprint "eagle-import:R0402-ARDUINO-ROUND")
      (libsource (lib "eagle-import") (part "R-EU_R0402-ARDUINO-ROUND"))
    )
    (comp (ref "R44")
      (value "0402/10K/5%")
      (footprint "eagle-import:R0402-ARDUINO-ROUND")
      (libsource (lib "eagle-import") (part "R-EU_R0402-ARDUINO-ROUND"))
    )
    (comp (ref "R45")
      (value "0402/12R/5%")
      (footprint "eagle-import:R0402-ARDUINO-ROUND")
      (libsource (lib "eagle-import") (part "R-EU_R0402-ARDUINO-ROUND"))
    )
    (comp (ref "R46")
      (value "0402/2K/5%")
      (footprint "eagle-import:R0402-ARDUINO-ROUND")
      (libsource (lib "eagle-import") (part "R-EU_R0402-ARDUINO-ROUND"))
    )
    (comp (ref "R47")
      (value "0402/10K/5%")
      (footprint "eagle-import:R0402-ARDUINO-ROUND")
      (libsource (lib "eagle-import") (part "R-EU_R0402-ARDUINO-ROUND"))
    )
    (comp (ref "R48")
      (value "0402/10K/5%")
      (footprint "eagle-import:R0402-ARDUINO-ROUND")
      (libsource (lib "eagle-import") (part "R-EU_R0402-ARDUINO-ROUND"))
    )
    (comp (ref "R49")
      (value "0402/10K/5%")
      (footprint "eagle-import:R0402-ARDUINO-ROUND")
      (libsource (lib "eagle-import") (part "R-EU_R0402-ARDUINO-ROUND"))
    )
    (comp (ref "R102")
      (value "0402/10K/5%")
      (footprint "eagle-import:R0402-ARDUINO-ROUND")
      (libsource (lib "eagle-import") (part "R-EU_R0402-ARDUINO-ROUND"))
    )
    (comp (ref "R104")
      (value "0402/100K/1%")
      (footprint "eagle-import:R0402-ARDUINO-ROUND")
      (libsource (lib "eagle-import") (part "R-EU_R0402-ARDUINO-ROUND"))
    )
    (comp (ref "R105")
      (value "0402/39R/1%")
      (footprint "eagle-import:R0402-ARDUINO-ROUND")
      (libsource (lib "eagle-import") (part "R-EU_R0402-ARDUINO-ROUND"))
    )
    (comp (ref "R106")
      (value "0402/39R/1%")
      (footprint "eagle-import:R0402-ARDUINO-ROUND")
      (libsource (lib "eagle-import") (part "R-EU_R0402-ARDUINO-ROUND"))
    )
    (comp (ref "R107")
      (value "0603/6K8/1%")
      (footprint "eagle-import:R0603-ROUND")
      (libsource (lib "eagle-import") (part "R-EU_R0603-ROUND"))
    )
    (comp (ref "R108")
      (value "0402/0R/5%/(NP)")
      (footprint "eagle-import:R0402-ARDUINO-ROUND")
      (libsource (lib "eagle-import") (part "R-EU_R0402-ARDUINO-ROUND"))
    )
    (comp (ref "RX")
      (value "0603/LED/RED")
      (footprint "eagle-import:LED-0805-CORRECT")
      (libsource (lib "eagle-import") (part "LED0805-CORRECT"))
    )
    (comp (ref "S1")
      (value "SKQGAKE010")
      (footprint "eagle-import:TACTILE_SWITCH_SMD")
      (libsource (lib "eagle-import") (part "TAC_SWITCHSMD"))
    )
    (comp (ref "S4")
      (value "SKQGAKE010")
      (footprint "eagle-import:TACTILE_SWITCH_SMD")
      (libsource (lib "eagle-import") (part "TAC_SWITCHSMD"))
    )
    (comp (ref "S5")
      (value "SKQGAKE010")
      (footprint "eagle-import:TACTILE_SWITCH_SMD")
      (libsource (lib "eagle-import") (part "TAC_SWITCHSMD"))
    )
    (comp (ref "S6")
      (value "SKQGAKE010")
      (footprint "eagle-import:TACTILE_SWITCH_SMD")
      (libsource (lib "eagle-import") (part "TAC_SWITCHSMD"))
    )
    (comp (ref "S7")
      (value "SKRHAAE010")
      (footprint "eagle-import:JOYSTICK_MULTICOMP")
      (libsource (lib "eagle-import") (part "JOYSTICK_MINI_MULTICOMP"))
    )
    (comp (ref "S8")
      (value "CUS-12TB")
      (footprint "eagle-import:SWITCH-SPST-SMD-A")
      (libsource (lib "eagle-import") (part "SWITCH-SPST-SMD-A"))
    )
    (comp (ref "S9")
      (value "3x6x2.5")
      (footprint "eagle-import:TACTILE_SWITCH_SMD_3X6X2.5H")
      (libsource (lib "eagle-import") (part "TAC_SWITCH1-3X6X2.5"))
    )
    (comp (ref "S10")
      (value "3x6x2.5")
      (footprint "eagle-import:TACTILE_SWITCH_SMD_3X6X2.5H")
      (libsource (lib "eagle-import") (part "TAC_SWITCH1-3X6X2.5"))
    )
    (comp (ref "SG1")
      (value "PKLCS1212E4001-R1")
      (footprint "eagle-import:BUZZER-PKLCS1212E")
      (libsource (lib "eagle-import") (part "BUZZER-PKLCS1212E"))
    )
    (comp (ref "SJ1")
      (value "SRF RESET")
      (footprint "eagle-import:SJ_2S-NO")
      (libsource (lib "eagle-import") (part "SOLDERJUMPERNO"))
    )
    (comp (ref "SJ2")
      (value "SRF ERASE")
      (footprint "eagle-import:SJ_2S-NO")
      (libsource (lib "eagle-import") (part "SOLDERJUMPERNO"))
    )
    (comp (ref "SJ3")
      (value "ISP_RESET")
      (footprint "eagle-import:SJ_3")
      (libsource (lib "eagle-import") (part "SOLDERJUMPER_2WAYS"))
    )
    (comp (ref "SJ4")
      (value "IR_TX")
      (footprint "eagle-import:SJ_2S-TRACE")
      (libsource (lib "eagle-import") (part "SOLDERJUMPERTRACE"))
    )
    (comp (ref "SJ5")
      (value "RESET SELECT")
      (footprint "eagle-import:SJ_3")
      (libsource (lib "eagle-import") (part "SOLDERJUMPER_2WAYS"))
    )
    (comp (ref "SJ6")
      (value "RESET BUTTON")
      (footprint "eagle-import:SJ_2S-NO")
      (libsource (lib "eagle-import") (part "SOLDERJUMPERNO"))
    )
    (comp (ref "SJ7")
      (value "Buzzer")
      (footprint "eagle-import:SJ_2S-TRACE")
      (libsource (lib "eagle-import") (part "SOLDERJUMPERTRACE"))
    )
    (comp (ref "SJ8")
      (value "AREF")
      (footprint "eagle-import:SJ_3")
      (libsource (lib "eagle-import") (part "SOLDERJUMPER_2WAYS"))
    )
    (comp (ref "SJ9")
      (value "FTDI Power")
      (footprint "eagle-import:SJ_2S-NO")
      (libsource (lib "eagle-import") (part "SOLDERJUMPERNO"))
    )
    (comp (ref "SJ10")
      (value "VDDIO")
      (footprint "eagle-import:SJ_3")
      (libsource (lib "eagle-import") (part "SOLDERJUMPER_2WAYS"))
    )
    (comp (ref "SJ11")
      (value "D0-5")
      (footprint "eagle-import:SJ_2S-NO")
      (libsource (lib "eagle-import") (part "SOLDERJUMPERNO"))
    )
    (comp (ref "TP1")
      (value "GND")
      (footprint "eagle-import:P1-13")
      (libsource (lib "eagle-import") (part "TPPAD1-13"))
    )
    (comp (ref "TP2")
      (value "SRF Reset")
      (footprint "eagle-import:B1,27")
      (libsource (lib "eagle-import") (part "TPB1,27"))
    )
    (comp (ref "TP3")
      (value "SRF Reset")
      (footprint "eagle-import:B1,27")
      (libsource (lib "eagle-import") (part "TPB1,27"))
    )
    (comp (ref "TP4")
      (value "D22")
      (footprint "eagle-import:B1,27")
      (libsource (lib "eagle-import") (part "TPB1,27"))
    )
    (comp (ref "TP5")
      (value "PB24")
      (footprint "eagle-import:B1,27")
      (libsource (lib "eagle-import") (part "TPB1,27"))
    )
    (comp (ref "TP6")
      (value "SS3")
      (footprint "eagle-import:B1,27")
      (libsource (lib "eagle-import") (part "TPB1,27"))
    )
    (comp (ref "TP7")
      (value "PB22")
      (footprint "eagle-import:B1,27")
      (libsource (lib "eagle-import") (part "TPB1,27"))
    )
    (comp (ref "TP8")
      (value "PC10")
      (footprint "eagle-import:B1,27")
      (libsource (lib "eagle-import") (part "TPB1,27"))
    )
    (comp (ref "TP9")
      (value "PC27")
      (footprint "eagle-import:B1,27")
      (libsource (lib "eagle-import") (part "TPB1,27"))
    )
    (comp (ref "TP10")
      (value "D23")
      (footprint "eagle-import:B1,27")
      (libsource (lib "eagle-import") (part "TPB1,27"))
    )
    (comp (ref "TP11")
      (value "TXD1")
      (footprint "eagle-import:B1,27")
      (libsource (lib "eagle-import") (part "TPB1,27"))
    )
    (comp (ref "TP12")
      (value "RXD1")
      (footprint "eagle-import:B1,27")
      (libsource (lib "eagle-import") (part "TPB1,27"))
    )
    (comp (ref "TP15")
      (value "TXD0")
      (footprint "eagle-import:B1,27")
      (libsource (lib "eagle-import") (part "TPB1,27"))
    )
    (comp (ref "TP16")
      (value "RXD0")
      (footprint "eagle-import:B1,27")
      (libsource (lib "eagle-import") (part "TPB1,27"))
    )
    (comp (ref "TP17")
      (value "D19")
      (footprint "eagle-import:P1-13")
      (libsource (lib "eagle-import") (part "TPPAD1-13"))
    )
    (comp (ref "TP18")
      (value "D18")
      (footprint "eagle-import:P1-13")
      (libsource (lib "eagle-import") (part "TPPAD1-13"))
    )
    (comp (ref "TP19")
      (value "3V3")
      (footprint "eagle-import:P1-13")
      (libsource (lib "eagle-import") (part "TPPAD1-13"))
    )
    (comp (ref "TP20")
      (value "PD6")
      (footprint "eagle-import:B1,27")
      (libsource (lib "eagle-import") (part "TPB1,27"))
    )
    (comp (ref "TP21")
      (value "PC17")
      (footprint "eagle-import:B1,27")
      (libsource (lib "eagle-import") (part "TPB1,27"))
    )
    (comp (ref "TP22")
      (value "PC12")
      (footprint "eagle-import:B1,27")
      (libsource (lib "eagle-import") (part "TPB1,27"))
    )
    (comp (ref "TP23")
      (value "PB19")
      (footprint "eagle-import:B1,27")
      (libsource (lib "eagle-import") (part "TPB1,27"))
    )
    (comp (ref "TP24")
      (value "PB18")
      (footprint "eagle-import:B1,27")
      (libsource (lib "eagle-import") (part "TPB1,27"))
    )
    (comp (ref "TP25")
      (value "PC1")
      (footprint "eagle-import:B1,27")
      (libsource (lib "eagle-import") (part "TPB1,27"))
    )
    (comp (ref "TP26")
      (value "PD10")
      (footprint "eagle-import:B1,27")
      (libsource (lib "eagle-import") (part "TPB1,27"))
    )
    (comp (ref "TP27")
      (value "PB10")
      (footprint "eagle-import:B1,27")
      (libsource (lib "eagle-import") (part "TPB1,27"))
    )
    (comp (ref "TX")
      (value "0603/LED/RED")
      (footprint "eagle-import:LED-0805-CORRECT")
      (libsource (lib "eagle-import") (part "LED0805-CORRECT"))
    )
    (comp (ref "U2")
      (value "JHD12864-G13BSW-OUTLINE")
      (footprint "eagle-import:JHD12864-G13BSW-OUTLINE")
      (libsource (lib "eagle-import") (part "JHD12864-G13BSW-OUTLINE"))
    )
    (comp (ref "X1")
      (value "12Mhz 13pF 30ppm (7pf caps)")
      (footprint "eagle-import:CRYSTAL-5X3.2")
      (libsource (lib "eagle-import") (part "CRYSTAL-5X3.2"))
    )
    (comp (ref "X2")
      (value "32.768Khz")
      (footprint "eagle-import:RESONATOR_EPSON_FC_145")
      (libsource (lib "eagle-import") (part "RESONATOR_EPSON_FC_145"))
    )
    (comp (ref "Z1")
      (value "CG0603MLC-05E")
      (footprint "eagle-import:CT_CN0603")
      (libsource (lib "eagle-import") (part "VARISTORCN0603"))
    )
    (comp (ref "Z2")
      (value "CG0603MLC-05E")
      (footprint "eagle-import:CT_CN0603")
      (libsource (lib "eagle-import") (part "VARISTORCN0603"))
    )
    (comp (ref "Z3")
      (value "CG0603MLC-05E")
      (footprint "eagle-import:CT_CN0603")
      (libsource (lib "eagle-import") (part "VARISTORCN0603"))
    )
  )
  (nets
    (net (code "1") (name "/3V3") (class "Default")
      (node (ref "C106") (pin "2") (pinfunction "2_2") (pintype "passive"))
      (node (ref "C2") (pin "2") (pinfunction "2_2") (pintype "passive"))
      (node (ref "C30") (pin "1") (pinfunction "1_1") (pintype "passive"))
      (node (ref "C32") (pin "2") (pinfunction "2_2") (pintype "passive"))
      (node (ref "C37") (pin "1") (pinfunction "1_1") (pintype "passive"))
      (node (ref "D2") (pin "2") (pinfunction "A2_2") (pintype "passive"))
      (node (ref "IC1") (pin "57") (pinfunction "VDDIN_57") (pintype "power_in"))
      (node (ref "IC3") (pin "9") (pinfunction "3V3_9") (pintype "power_in"))
      (node (ref "IC5") (pin "3") (pinfunction "WP_3") (pintype "bidirectional"))
      (node (ref "IC5") (pin "8") (pinfunction "VCC_8") (pintype "bidirectional"))
      (node (ref "IC8") (pin "4") (pinfunction "VOUT_4") (pintype "output"))
      (node (ref "J3") (pin "3V") (pinfunction "3V_3V") (pintype "power_in"))
      (node (ref "J3") (pin "IOREF") (pinfunction "IOREF_IOREF") (pintype "output"))
      (node (ref "J5") (pin "P4") (pinfunction "VCC_P4") (pintype "bidirectional"))
      (node (ref "J6") (pin "1") (pinfunction "VIN_1") (pintype "bidirectional"))
      (node (ref "JP2") (pin "1") (pinfunction "1_1") (pintype "passive"))
      (node (ref "JP8") (pin "2") (pinfunction "2_2") (pintype "passive"))
      (node (ref "LED1") (pin "A") (pinfunction "ANODE_A") (pintype "passive"))
      (node (ref "LED2") (pin "A") (pinfunction "ANODE_A") (pintype "passive"))
      (node (ref "Q11") (pin "2") (pinfunction "S_2") (pintype "bidirectional"))
      (node (ref "Q13") (pin "2") (pinfunction "S_2") (pintype "bidirectional"))
      (node (ref "R26") (pin "2") (pinfunction "2_2") (pintype "passive"))
      (node (ref "R4") (pin "2") (pinfunction "2_2") (pintype "passive"))
      (node (ref "SJ10") (pin "1") (pinfunction "1_1") (pintype "passive"))
      (node (ref "SJ9") (pin "2") (pinfunction "2_2") (pintype "passive"))
      (node (ref "TP19") (pin "TP") (pinfunction "TP_TP") (pintype "input"))
      (node (ref "U2") (pin "A") (pinfunction "A_A") (pintype "bidirectional"))
    )
    (net (code "2") (name "/5V0") (class "Default")
      (node (ref "J3") (pin "5V") (pinfunction "5V_5V") (pintype "power_in"))
      (node (ref "J3") (pin "5V@ISP") (pinfunction "5V_5V@ISP") (pintype "power_in"))
      (node (ref "J6") (pin "3") (pinfunction "VOUT_3") (pintype "bidirectional"))
      (node (ref "JP7") (pin "14") (pinfunction "14_14") (pintype "passive"))
    )
    (net (code "3") (name "/A63") (class "Default")
      (node (ref "IC1") (pin "89") (pinfunction "PB18_89") (pintype "bidirectional"))
      (node (ref "TP24") (pin "TP") (pinfunction "TP_TP") (pintype "input"))
    )
    (net (code "4") (name "/A64") (class "Default")
      (node (ref "IC1") (pin "90") (pinfunction "PB19_90") (pintype "bidirectional"))
      (node (ref "TP23") (pin "TP") (pinfunction "TP_TP") (pintype "input"))
    )
    (net (code "5") (name "/AD0") (class "Default")
      (node (ref "IC1") (pin "78") (pinfunction "PA16_78") (pintype "bidirectional"))
      (node (ref "J3") (pin "A0") (pinfunction "A0_A0") (pintype "bidirectional"))
    )
    (net (code "6") (name "/AD1") (class "Default")
      (node (ref "IC1") (pin "79") (pinfunction "PA24_79") (pintype "bidirectional"))
      (node (ref "J3") (pin "A1") (pinfunction "A1_A1") (pintype "bidirectional"))
    )
    (net (code "7") (name "/AD2") (class "Default")
      (node (ref "IC1") (pin "80") (pinfunction "PA23_80") (pintype "bidirectional"))
      (node (ref "J3") (pin "A2") (pinfunction "A2_A2") (pintype "bidirectional"))
    )
    (net (code "8") (name "/AD3") (class "Default")
      (node (ref "IC1") (pin "81") (pinfunction "PA22_81") (pintype "bidirectional"))
      (node (ref "J3") (pin "A3") (pinfunction "A3_A3") (pintype "bidirectional"))
    )
    (net (code "9") (name "/AD4") (class "Default")
      (node (ref "IC1") (pin "82") (pinfunction "PA6_82") (pintype "bidirectional"))
      (node (ref "J3") (pin "A4") (pinfunction "A4_A4") (pintype "bidirectional"))
    )
    (net (code "10") (name "/AD5") (class "Default")
      (node (ref "IC1") (pin "83") (pinfunction "PA4_83") (pintype "bidirectional"))
      (node (ref "J3") (pin "A5") (pinfunction "A5_A5") (pintype "bidirectional"))
    )
    (net (code "11") (name "/ANT") (class "Default")
      (node (ref "IC3") (pin "8") (pinfunction "ANT_8") (pintype "output"))
      (node (ref "JP3") (pin "TP") (pinfunction "TP_TP") (pintype "input"))
    )
    (net (code "12") (name "/AREF") (class "Default")
      (node (ref "J3") (pin "AREF") (pinfunction "AREF_AREF") (pintype "bidirectional"))
      (node (ref "SJ8") (pin "1") (pinfunction "1_1") (pintype "passive"))
    )
    (net (code "13") (name "/AVREF") (class "Default")
      (node (ref "C119") (pin "2") (pinfunction "2_2") (pintype "passive"))
      (node (ref "IC1") (pin "75") (pinfunction "ADVREF_75") (pintype "power_in"))
      (node (ref "L103") (pin "2") (pinfunction "2_2") (pintype "passive"))
    )
    (net (code "14") (name "/BP") (class "Default")
      (node (ref "IC9") (pin "4") (pinfunction "BP_4") (pintype "input"))
    )
    (net (code "15") (name "/BUTTON_A") (class "Default")
      (node (ref "IC1") (pin "97") (pinfunction "PC15_97") (pintype "bidirectional"))
      (node (ref "S10") (pin "1") (pinfunction "1_1") (pintype "passive"))
      (node (ref "S6") (pin "3") (pinfunction "3_3") (pintype "passive"))
      (node (ref "S6") (pin "4") (pinfunction "4_4") (pintype "passive"))
    )
    (net (code "16") (name "/BUTTON_B") (class "Default")
      (node (ref "IC1") (pin "98") (pinfunction "PC16_98") (pintype "bidirectional"))
      (node (ref "S5") (pin "1") (pinfunction "1_1") (pintype "passive"))
      (node (ref "S5") (pin "2") (pinfunction "2_2") (pintype "passive"))
      (node (ref "S9") (pin "1") (pinfunction "1_1") (pintype "passive"))
    )
    (net (code "17") (name "/BUTTON_CENTER") (class "Default")
      (node (ref "IC1") (pin "8") (pinfunction "PA15_8") (pintype "bidirectional"))
      (node (ref "R48") (pin "1") (pinfunction "1_1") (pintype "passive"))
      (node (ref "S7") (pin "CTR") (pinfunction "CENT_CTR") (pintype "bidirectional"))
    )
    (net (code "18") (name "/BUTTON_DOWN") (class "Default")
      (node (ref "IC1") (pin "14") (pinfunction "PD1_14") (pintype "bidirectional"))
      (node (ref "S7") (pin "D") (pinfunction "DOWN_D") (pintype "bidirectional"))
    )
    (net (code "19") (name "/BUTTON_LEFT") (class "Default")
      (node (ref "IC1") (pin "16") (pinfunction "PD3_16") (pintype "bidirectional"))
      (node (ref "S7") (pin "C") (pinfunction "RIGHT_C") (pintype "bidirectional"))
    )
    (net (code "20") (name "/BUTTON_RIGHT") (class "Default")
      (node (ref "IC1") (pin "13") (pinfunction "PD0_13") (pintype "bidirectional"))
      (node (ref "S7") (pin "B") (pinfunction "LEFT_B") (pintype "bidirectional"))
    )
    (net (code "21") (name "/BUTTON_UP") (class "Default")
      (node (ref "IC1") (pin "15") (pinfunction "PD2_15") (pintype "bidirectional"))
      (node (ref "S7") (pin "A") (pinfunction "UP_A") (pintype "bidirectional"))
    )
    (net (code "22") (name "/C1") (class "Default")
      (node (ref "C28") (pin "2") (pinfunction "2_2") (pintype "passive"))
      (node (ref "IC7") (pin "10") (pinfunction "C1_10") (pintype "bidirectional"))
    )
    (net (code "23") (name "/CANRX0") (class "Default")
      (node (ref "IC1") (pin "24") (pinfunction "PA1_24") (pintype "bidirectional"))
      (node (ref "JP5") (pin "2") (pinfunction "2_2") (pintype "passive"))
    )
    (net (code "24") (name "/CANTX0") (class "Default")
      (node (ref "IC1") (pin "23") (pinfunction "PA0_23") (pintype "bidirectional"))
      (node (ref "JP5") (pin "1") (pinfunction "1_1") (pintype "passive"))
    )
    (net (code "25") (name "/D22") (class "Default")
      (node (ref "IC1") (pin "1") (pinfunction "PB26_1") (pintype "bidirectional"))
      (node (ref "TP4") (pin "TP") (pinfunction "TP_TP") (pintype "input"))
    )
    (net (code "26") (name "/D23") (class "Default")
      (node (ref "IC1") (pin "7") (pinfunction "PA14_7") (pintype "bidirectional"))
      (node (ref "TP10") (pin "TP") (pinfunction "TP_TP") (pintype "input"))
    )
    (net (code "27") (name "/D33") (class "Default")
      (node (ref "IC1") (pin "55") (pinfunction "PC1_55") (pintype "bidirectional"))
      (node (ref "TP25") (pin "TP") (pinfunction "TP_TP") (pintype "input"))
    )
    (net (code "28") (name "/D51") (class "Default")
      (node (ref "IC1") (pin "94") (pinfunction "PC12_94") (pintype "bidirectional"))
      (node (ref "TP22") (pin "TP") (pinfunction "TP_TP") (pintype "input"))
    )
    (net (code "29") (name "/DAC0") (class "Default")
      (node (ref "IC1") (pin "76") (pinfunction "PB15_76") (pintype "bidirectional"))
      (node (ref "JP4") (pin "2") (pinfunction "2_2") (pintype "passive"))
      (node (ref "SJ7") (pin "2") (pinfunction "2_2") (pintype "passive"))
    )
    (net (code "30") (name "/DAC1") (class "Default")
      (node (ref "IC1") (pin "77") (pinfunction "PB16_77") (pintype "bidirectional"))
      (node (ref "JP4") (pin "1") (pinfunction "1_1") (pintype "passive"))
    )
    (net (code "31") (name "/DFSD_N") (class "Default")
      (node (ref "IC1") (pin "43") (pinfunction "DFSDM_43") (pintype "input"))
      (node (ref "R105") (pin "2") (pinfunction "2_2") (pintype "passive"))
    )
    (net (code "32") (name "/DFSD_P") (class "Default")
      (node (ref "IC1") (pin "42") (pinfunction "DFSDP_42") (pintype "input"))
      (node (ref "R106") (pin "2") (pinfunction "2_2") (pintype "passive"))
    )
    (net (code "33") (name "/DHSD_N") (class "Default")
      (node (ref "IC1") (pin "38") (pinfunction "DHSDM_38") (pintype "bidirectional"))
      (node (ref "J1") (pin "D-") (pinfunction "D-_D-") (pintype "bidirectional"))
      (node (ref "R105") (pin "1") (pinfunction "1_1") (pintype "passive"))
      (node (ref "Z2") (pin "1") (pinfunction "1_1") (pintype "passive"))
    )
    (net (code "34") (name "/DHSD_P") (class "Default")
      (node (ref "IC1") (pin "37") (pinfunction "DHSDP_37") (pintype "bidirectional"))
      (node (ref "J1") (pin "D+") (pinfunction "D+_D+") (pintype "bidirectional"))
      (node (ref "R106") (pin "1") (pinfunction "1_1") (pintype "passive"))
      (node (ref "Z1") (pin "1") (pinfunction "1_1") (pintype "passive"))
    )
    (net (code "35") (name "/DTR") (class "Default")
      (node (ref "C29") (pin "2") (pinfunction "2_2") (pintype "passive"))
      (node (ref "JP6") (pin "6") (pinfunction "6_6") (pintype "passive"))
    )
    (net (code "36") (name "/EEXTINT") (class "Default")
      (node (ref "IC1") (pin "25") (pinfunction "PA5_25") (pintype "bidirectional"))
      (node (ref "JP7") (pin "11") (pinfunction "11_11") (pintype "passive"))
    )
    (net (code "37") (name "/EMDC") (class "Default")
      (node (ref "IC1") (pin "123") (pinfunction "PB8_123") (pintype "bidirectional"))
      (node (ref "JP7") (pin "5") (pinfunction "5_5") (pintype "passive"))
    )
    (net (code "38") (name "/EMDIO") (class "Default")
      (node (ref "IC1") (pin "127") (pinfunction "PB9_127") (pintype "bidirectional"))
      (node (ref "JP7") (pin "7") (pinfunction "7_7") (pintype "passive"))
    )
    (net (code "39") (name "/ERASE_CMD") (class "Default")
      (node (ref "Q8") (pin "1") (pinfunction "G_1") (pintype "bidirectional"))
      (node (ref "R41") (pin "1") (pinfunction "1_1") (pintype "passive"))
      (node (ref "SJ2") (pin "2") (pinfunction "2_2") (pintype "passive"))
    )
    (net (code "40") (name "/ERASE_S") (class "Default")
      (node (ref "IC1") (pin "130") (pinfunction "PC0_130") (pintype "bidirectional"))
      (node (ref "JP1") (pin "1") (pinfunction "1_1") (pintype "passive"))
      (node (ref "Q8") (pin "3") (pinfunction "D_3") (pintype "bidirectional"))
    )
    (net (code "41") (name "/ERXD0") (class "Default")
      (node (ref "IC1") (pin "120") (pinfunction "PB5_120") (pintype "bidirectional"))
      (node (ref "JP7") (pin "6") (pinfunction "6_6") (pintype "passive"))
    )
    (net (code "42") (name "/ERXD1") (class "Default")
      (node (ref "IC1") (pin "121") (pinfunction "PB6_121") (pintype "bidirectional"))
      (node (ref "JP7") (pin "1") (pinfunction "1_1") (pintype "passive"))
    )
    (net (code "43") (name "/ERX_DV") (class "Default")
      (node (ref "IC1") (pin "119") (pinfunction "PB4_119") (pintype "bidirectional"))
      (node (ref "JP7") (pin "4") (pinfunction "4_4") (pintype "passive"))
    )
    (net (code "44") (name "/ERX_ER") (class "Default")
      (node (ref "IC1") (pin "122") (pinfunction "PB7_122") (pintype "bidirectional"))
      (node (ref "JP7") (pin "3") (pinfunction "3_3") (pintype "passive"))
    )
    (net (code "45") (name "/ETXD0") (class "Default")
      (node (ref "IC1") (pin "115") (pinfunction "PB2_115") (pintype "bidirectional"))
      (node (ref "JP7") (pin "8") (pinfunction "8_8") (pintype "passive"))
    )
    (net (code "46") (name "/ETXD1") (class "Default")
      (node (ref "IC1") (pin "118") (pinfunction "PB3_118") (pintype "bidirectional"))
      (node (ref "JP7") (pin "2") (pinfunction "2_2") (pintype "passive"))
    )
    (net (code "47") (name "/ETX_CLK") (class "Default")
      (node (ref "IC1") (pin "113") (pinfunction "PB0_113") (pintype "bidirectional"))
      (node (ref "JP7") (pin "12") (pinfunction "12_12") (pintype "passive"))
    )
    (net (code "48") (name "/ETX_EN") (class "Default")
      (node (ref "IC1") (pin "114") (pinfunction "PB1_114") (pintype "bidirectional"))
      (node (ref "JP7") (pin "10") (pinfunction "10_10") (pintype "passive"))
    )
    (net (code "50") (name "/FLASH_CS") (class "Default")
      (node (ref "IC1") (pin "111") (pinfunction "PA28_111") (pintype "bidirectional"))
      (node (ref "IC5") (pin "1") (pinfunction "CS_1") (pintype "bidirectional"))
    )
    (net (code "51") (name "/FLASH_HOLD") (class "Default")
      (node (ref "IC1") (pin "96") (pinfunction "PC14_96") (pintype "bidirectional"))
      (node (ref "IC5") (pin "7") (pinfunction "HOLD_7") (pintype "bidirectional"))
    )
    (net (code "52") (name "/FTDI_PWR") (class "Default")
      (node (ref "C38") (pin "2") (pinfunction "2_2") (pintype "passive"))
      (node (ref "JP6") (pin "3") (pinfunction "3_3") (pintype "passive"))
      (node (ref "SJ9") (pin "1") (pinfunction "1_1") (pintype "passive"))
    )
    (net (code "53") (name "/HMC_DRDY") (class "Default")
      (node (ref "IC1") (pin "22") (pinfunction "PD9_22") (pintype "bidirectional"))
      (node (ref "IC7") (pin "15") (pinfunction "DRDY_15") (pintype "bidirectional"))
    )
    (net (code "54") (name "/IR_RX") (class "Default")
      (node (ref "IC1") (pin "71") (pinfunction "PA19_71") (pintype "bidirectional"))
      (node (ref "IR_RX") (pin "3") (pinfunction "OUT_3") (pintype "bidirectional"))
    )
    (net (code "55") (name "/IR_RX_PWR") (class "Default")
      (node (ref "IC1") (pin "95") (pinfunction "PC13_95") (pintype "bidirectional"))
      (node (ref "Q13") (pin "1") (pinfunction "G_1") (pintype "bidirectional"))
      (node (ref "R49") (pin "2") (pinfunction "2_2") (pintype "passive"))
    )
    (net (code "56") (name "/IR_TX_PWM") (class "Default")
      (node (ref "Q9") (pin "1") (pinfunction "G_1") (pintype "bidirectional"))
      (node (ref "R40") (pin "1") (pinfunction "1_1") (pintype "passive"))
      (node (ref "SJ4") (pin "1") (pinfunction "1_1") (pintype "passive"))
    )
    (net (code "57") (name "/ISP_~{RESET}") (class "Default")
      (node (ref "J3") (pin "!RESET@ISP") (pinfunction "~{RESET}_!RESET@ISP") (pintype "bidirectional"))
      (node (ref "Q10") (pin "3") (pinfunction "D_3") (pintype "bidirectional"))
      (node (ref "SJ3") (pin "1") (pinfunction "1_1") (pintype "passive"))
      (node (ref "SJ3") (pin "2") (pinfunction "2_2") (pintype "passive"))
    )
    (net (code "58") (name "/ISP_~{RESET}_IO") (class "Default")
      (node (ref "IC1") (pin "140") (pinfunction "PB14_140") (pintype "bidirectional"))
      (node (ref "Q10") (pin "1") (pinfunction "G_1") (pintype "bidirectional"))
      (node (ref "R42") (pin "1") (pinfunction "1_1") (pintype "passive"))
    )
    (net (code "59") (name "/JTAG_RESET") (class "Default")
      (node (ref "JP2") (pin "10") (pinfunction "10_10") (pintype "passive"))
      (node (ref "R24") (pin "1") (pinfunction "1_1") (pintype "passive"))
      (node (ref "R7") (pin "1") (pinfunction "1_1") (pintype "passive"))
    )
    (net (code "60") (name "/JTAG_TCK") (class "Default")
      (node (ref "IC1") (pin "28") (pinfunction "PB28_28") (pintype "bidirectional"))
      (node (ref "JP2") (pin "4") (pinfunction "4_4") (pintype "passive"))
      (node (ref "R22") (pin "1") (pinfunction "1_1") (pintype "passive"))
    )
    (net (code "61") (name "/JTAG_TDI") (class "Default")
      (node (ref "IC1") (pin "29") (pinfunction "PB29_29") (pintype "bidirectional"))
      (node (ref "JP2") (pin "8") (pinfunction "8_8") (pintype "passive"))
      (node (ref "R23") (pin "1") (pinfunction "1_1") (pintype "passive"))
    )
    (net (code "62") (name "/JTAG_TDO") (class "Default")
      (node (ref "IC1") (pin "30") (pinfunction "PB30_30") (pintype "bidirectional"))
      (node (ref "JP2") (pin "6") (pinfunction "6_6") (pintype "passive"))
    )
    (net (code "63") (name "/JTAG_TMS") (class "Default")
      (node (ref "IC1") (pin "31") (pinfunction "PB31_31") (pintype "bidirectional"))
      (node (ref "JP2") (pin "2") (pinfunction "2_2") (pintype "passive"))
      (node (ref "R21") (pin "1") (pinfunction "1_1") (pintype "passive"))
    )
    (net (code "64") (name "/LCD_3V3") (class "Default")
      (node (ref "J7") (pin "15") (pinfunction "VDD_15") (pintype "bidirectional"))
      (node (ref "J7") (pin "28") (pinfunction "C86_28") (pintype "bidirectional"))
      (node (ref "J7") (pin "5") (pinfunction "WR_5") (pintype "bidirectional"))
      (node (ref "J7") (pin "6") (pinfunction "RD_6") (pintype "bidirectional"))
      (node (ref "Q11") (pin "3") (pinfunction "D_3") (pintype "bidirectional"))
      (node (ref "SJ11") (pin "1") (pinfunction "1_1") (pintype "passive"))
    )
    (net (code "65") (name "/LCD_A0") (class "Default")
      (node (ref "IC1") (pin "64") (pinfunction "PC6_64") (pintype "bidirectional"))
      (node (ref "J7") (pin "4") (pinfunction "A0_4") (pintype "bidirectional"))
    )
    (net (code "66") (name "/LCD_BACKLIGHT") (class "Default")
      (node (ref "IC1") (pin "60") (pinfunction "PC3_60") (pintype "bidirectional"))
      (node (ref "Q12") (pin "1") (pinfunction "G_1") (pintype "bidirectional"))
      (node (ref "R43") (pin "1") (pinfunction "1_1") (pintype "passive"))
    )
    (net (code "67") (name "/LCD_P1+") (class "Default")
      (node (ref "C41") (pin "2") (pinfunction "2_2") (pintype "passive"))
      (node (ref "J7") (pin "20") (pinfunction "P1+_20") (pintype "bidirectional"))
    )
    (net (code "68") (name "/LCD_P1-") (class "Default")
      (node (ref "C40") (pin "1") (pinfunction "1_1") (pintype "passive"))
      (node (ref "C41") (pin "1") (pinfunction "1_1") (pintype "passive"))
      (node (ref "J7") (pin "19") (pinfunction "P1-_19") (pintype "bidirectional"))
    )
    (net (code "69") (name "/LCD_P2+") (class "Default")
      (node (ref "C42") (pin "2") (pinfunction "2_2") (pintype "passive"))
      (node (ref "J7") (pin "21") (pinfunction "P2+_21") (pintype "bidirectional"))
    )
    (net (code "70") (name "/LCD_P2-") (class "Default")
      (node (ref "C42") (pin "1") (pinfunction "1_1") (pintype "passive"))
      (node (ref "J7") (pin "22") (pinfunction "P2-_22") (pintype "bidirectional"))
    )
    (net (code "71") (name "/LCD_P3+") (class "Default")
      (node (ref "C40") (pin "2") (pinfunction "2_2") (pintype "passive"))
      (node (ref "J7") (pin "18") (pinfunction "P3+_18") (pintype "bidirectional"))
    )
    (net (code "72") (name "/LCD_POWER") (class "Default")
      (node (ref "IC1") (pin "66") (pinfunction "PC8_66") (pintype "bidirectional"))
      (node (ref "Q11") (pin "1") (pinfunction "G_1") (pintype "bidirectional"))
      (node (ref "R44") (pin "1") (pinfunction "1_1") (pintype "passive"))
    )
    (net (code "73") (name "/LCD_V0") (class "Default")
      (node (ref "C47") (pin "2") (pinfunction "2_2") (pintype "passive"))
      (node (ref "J7") (pin "27") (pinfunction "V0_27") (pintype "bidirectional"))
    )
    (net (code "74") (name "/LCD_V1") (class "Default")
      (node (ref "C46") (pin "2") (pinfunction "2_2") (pintype "passive"))
      (node (ref "J7") (pin "26") (pinfunction "V1_26") (pintype "bidirectional"))
    )
    (net (code "75") (name "/LCD_V2") (class "Default")
      (node (ref "C45") (pin "2") (pinfunction "2_2") (pintype "passive"))
      (node (ref "J7") (pin "25") (pinfunction "V2_25") (pintype "bidirectional"))
    )
    (net (code "76") (name "/LCD_V3") (class "Default")
      (node (ref "C44") (pin "2") (pinfunction "2_2") (pintype "passive"))
      (node (ref "J7") (pin "24") (pinfunction "V3_24") (pintype "bidirectional"))
    )
    (net (code "77") (name "/LCD_V4") (class "Default")
      (node (ref "C43") (pin "2") (pinfunction "2_2") (pintype "passive"))
      (node (ref "J7") (pin "23") (pinfunction "V4_23") (pintype "bidirectional"))
    )
    (net (code "78") (name "/LCD_VOUT") (class "Default")
      (node (ref "C39") (pin "2") (pinfunction "2_2") (pintype "passive"))
      (node (ref "J7") (pin "17") (pinfunction "VOUT_17") (pintype "bidirectional"))
    )
    (net (code "79") (name "/LCD_~{CS}") (class "Default")
      (node (ref "IC1") (pin "92") (pinfunction "PB21_92") (pintype "bidirectional"))
      (node (ref "J7") (pin "2") (pinfunction "CS1B_2") (pintype "bidirectional"))
    )
    (net (code "80") (name "/LCD_~{RST}") (class "Default")
      (node (ref "IC1") (pin "59") (pinfunction "PC2_59") (pintype "bidirectional"))
      (node (ref "J7") (pin "3") (pinfunction "RST_3") (pintype "bidirectional"))
    )
    (net (code "81") (name "/LED1_BLUE") (class "Default")
      (node (ref "IC1") (pin "67") (pinfunction "PC9_67") (pintype "bidirectional"))
      (node (ref "R18") (pin "2") (pinfunction "2_2") (pintype "passive"))
    )
    (net (code "82") (name "/LED1_GREEN") (class "Default")
      (node (ref "IC1") (pin "65") (pinfunction "PC7_65") (pintype "bidirectional"))
      (node (ref "R19") (pin "2") (pinfunction "2_2") (pintype "passive"))
    )
    (net (code "83") (name "/LED1_RED") (class "Default")
      (node (ref "IC1") (pin "63") (pinfunction "PC5_63") (pintype "bidirectional"))
      (node (ref "R20") (pin "2") (pinfunction "2_2") (pintype "passive"))
    )
    (net (code "84") (name "/LED2_BLUE") (class "Default")
      (node (ref "IC1") (pin "100") (pinfunction "PC18_100") (pintype "bidirectional"))
      (node (ref "R15") (pin "2") (pinfunction "2_2") (pintype "passive"))
    )
    (net (code "85") (name "/LED2_GREEN") (class "Default")
      (node (ref "IC1") (pin "101") (pinfunction "PC19_101") (pintype "bidirectional"))
      (node (ref "R16") (pin "2") (pinfunction "2_2") (pintype "passive"))
    )
    (net (code "86") (name "/LED2_RED") (class "Default")
      (node (ref "IC1") (pin "131") (pinfunction "PC20_131") (pintype "bidirectional"))
      (node (ref "R17") (pin "2") (pinfunction "2_2") (pintype "passive"))
    )
    (net (code "87") (name "/LIGHT") (class "Default")
      (node (ref "IC1") (pin "84") (pinfunction "PA3_84") (pintype "bidirectional"))
      (node (ref "R47") (pin "1") (pinfunction "1_1") (pintype "passive"))
      (node (ref "S1") (pin "1") (pinfunction "1_1") (pintype "passive"))
      (node (ref "S1") (pin "2") (pinfunction "2_2") (pintype "passive"))
    )
    (net (code "88") (name "/MASTER_RESET") (class "Default")
      (node (ref "C29") (pin "1") (pinfunction "1_1") (pintype "passive"))
      (node (ref "J3") (pin "!RESET") (pinfunction "~{RESET}_!RESET") (pintype "bidirectional"))
      (node (ref "R7") (pin "2") (pinfunction "2_2") (pintype "passive"))
      (node (ref "SJ1") (pin "2") (pinfunction "2_2") (pintype "passive"))
      (node (ref "SJ3") (pin "3") (pinfunction "3_3") (pintype "passive"))
      (node (ref "SJ5") (pin "2") (pinfunction "2_2") (pintype "passive"))
      (node (ref "SJ6") (pin "1") (pinfunction "1_1") (pintype "passive"))
    )
    (net (code "89") (name "/MCP_STAT") (class "Default")
      (node (ref "IC1") (pin "88") (pinfunction "PB17_88") (pintype "bidirectional"))
      (node (ref "IC10") (pin "1") (pinfunction "STAT_1") (pintype "output"))
    )
    (net (code "90") (name "/MISO") (class "Default")
      (node (ref "IC1") (pin "108") (pinfunction "PA25_108") (pintype "bidirectional"))
      (node (ref "IC5") (pin "2") (pinfunction "MISO_2") (pintype "bidirectional"))
      (node (ref "J3") (pin "MISO") (pinfunction "MISO_MISO") (pintype "bidirectional"))
      (node (ref "J5") (pin "P7") (pinfunction "DO_P7") (pintype "bidirectional"))
    )
    (net (code "91") (name "/MOSI") (class "Default")
      (node (ref "IC1") (pin "109") (pinfunction "PA26_109") (pintype "bidirectional"))
      (node (ref "IC5") (pin "5") (pinfunction "MOSI_5") (pintype "bidirectional"))
      (node (ref "J3") (pin "MOSI") (pinfunction "MOSI_MOSI") (pintype "bidirectional"))
      (node (ref "J5") (pin "P3") (pinfunction "DI_P3") (pintype "bidirectional"))
      (node (ref "J7") (pin "14") (pinfunction "D7_14") (pintype "bidirectional"))
    )
    (net (code "92") (name "/MPU_AUX_CL") (class "Default")
      (node (ref "IC2") (pin "7") (pinfunction "AUX_CL_7") (pintype "bidirectional"))
      (node (ref "IC7") (pin "1") (pinfunction "SCL_1") (pintype "bidirectional"))
    )
    (net (code "93") (name "/MPU_AUX_DA") (class "Default")
      (node (ref "IC2") (pin "6") (pinfunction "AUX_DA_6") (pintype "bidirectional"))
      (node (ref "IC7") (pin "16") (pinfunction "SDA_16") (pintype "bidirectional"))
    )
    (net (code "94") (name "/MPU_CPOUT") (class "Default")
      (node (ref "C5") (pin "1") (pinfunction "1_1") (pintype "passive"))
      (node (ref "IC2") (pin "20") (pinfunction "CPOUT_20") (pintype "bidirectional"))
    )
    (net (code "95") (name "/MPU_INT") (class "Default")
      (node (ref "IC1") (pin "26") (pinfunction "PA7_26") (pintype "bidirectional"))
      (node (ref "IC2") (pin "12") (pinfunction "INT_12") (pintype "bidirectional"))
    )
    (net (code "96") (name "/MPU_REGOUT") (class "Default")
      (node (ref "C6") (pin "1") (pinfunction "1_1") (pintype "passive"))
      (node (ref "IC2") (pin "10") (pinfunction "REGOUT_10") (pintype "bidirectional"))
    )
    (net (code "97") (name "/NRST") (class "Default")
      (node (ref "IC1") (pin "69") (pinfunction "NRST_69") (pintype "bidirectional"))
      (node (ref "JP7") (pin "9") (pinfunction "9_9") (pintype "passive"))
      (node (ref "SJ5") (pin "3") (pinfunction "3_3") (pintype "passive"))
    )
    (net (code "98") (name "/NRSTB") (class "Default")
      (node (ref "C120") (pin "2") (pinfunction "2_2") (pintype "passive"))
      (node (ref "IC1") (pin "47") (pinfunction "NRSTB_47") (pintype "input"))
      (node (ref "SJ5") (pin "1") (pinfunction "1_1") (pintype "passive"))
    )
    (net (code "99") (name "/PB22") (class "Default")
      (node (ref "IC1") (pin "141") (pinfunction "PB22_141") (pintype "bidirectional"))
      (node (ref "TP7") (pin "TP") (pinfunction "TP_TP") (pintype "input"))
    )
    (net (code "100") (name "/PB24") (class "Default")
      (node (ref "IC1") (pin "143") (pinfunction "PB24_143") (pintype "bidirectional"))
      (node (ref "TP5") (pin "TP") (pinfunction "TP_TP") (pintype "input"))
    )
    (net (code "101") (name "/PC10") (class "Default")
      (node (ref "IC1") (pin "117") (pinfunction "PC10_117") (pintype "bidirectional"))
      (node (ref "TP8") (pin "TP") (pinfunction "TP_TP") (pintype "input"))
    )
    (net (code "102") (name "/PC11") (class "Default")
      (node (ref "IC1") (pin "93") (pinfunction "PC11_93") (pintype "bidirectional"))
      (node (ref "JP7") (pin "13") (pinfunction "13_13") (pintype "passive"))
    )
    (net (code "103") (name "/PC27") (class "Default")
      (node (ref "IC1") (pin "138") (pinfunction "PC27_138") (pintype "bidirectional"))
      (node (ref "TP9") (pin "TP") (pinfunction "TP_TP") (pintype "input"))
    )
    (net (code "104") (name "/PD10") (class "Default")
      (node (ref "IC1") (pin "32") (pinfunction "PD10_32") (pintype "bidirectional"))
      (node (ref "TP26") (pin "TP") (pinfunction "TP_TP") (pintype "input"))
    )
    (net (code "105") (name "/PROG") (class "Default")
      (node (ref "IC10") (pin "5") (pinfunction "PROG_5") (pintype "input"))
      (node (ref "R46") (pin "1") (pinfunction "1_1") (pintype "passive"))
    )
    (net (code "106") (name "/PWM2") (class "Default")
      (node (ref "IC1") (pin "144") (pinfunction "PB25_144") (pintype "bidirectional"))
      (node (ref "J3") (pin "D2") (pinfunction "D2_D2") (pintype "bidirectional"))
    )
    (net (code "107") (name "/PWM3") (class "Default")
      (node (ref "IC1") (pin "139") (pinfunction "PC28_139") (pintype "bidirectional"))
      (node (ref "J3") (pin "D3") (pinfunction "D3_D3") (pintype "bidirectional"))
    )
    (net (code "108") (name "/PWM4") (class "Default")
      (node (ref "IC1") (pin "137") (pinfunction "PC26_137") (pintype "bidirectional"))
      (node (ref "J3") (pin "D4") (pinfunction "D4_D4") (pintype "bidirectional"))
    )
    (net (code "109") (name "/PWM5") (class "Default")
      (node (ref "IC1") (pin "136") (pinfunction "PC25_136") (pintype "bidirectional"))
      (node (ref "J3") (pin "D5") (pinfunction "D5_D5") (pintype "bidirectional"))
    )
    (net (code "110") (name "/PWM6") (class "Default")
      (node (ref "IC1") (pin "135") (pinfunction "PC24_135") (pintype "bidirectional"))
      (node (ref "J3") (pin "D6") (pinfunction "D6_D6") (pintype "bidirectional"))
      (node (ref "SJ4") (pin "2") (pinfunction "2_2") (pintype "passive"))
    )
    (net (code "111") (name "/PWM7") (class "Default")
      (node (ref "IC1") (pin "134") (pinfunction "PC23_134") (pintype "bidirectional"))
      (node (ref "J3") (pin "D7") (pinfunction "D7_D7") (pintype "bidirectional"))
    )
    (net (code "112") (name "/PWM8") (class "Default")
      (node (ref "IC1") (pin "133") (pinfunction "PC22_133") (pintype "bidirectional"))
      (node (ref "J3") (pin "D8") (pinfunction "D8_D8") (pintype "bidirectional"))
    )
    (net (code "113") (name "/PWM9") (class "Default")
      (node (ref "IC1") (pin "132") (pinfunction "PC21_132") (pintype "bidirectional"))
      (node (ref "J3") (pin "D9") (pinfunction "D9_D9") (pintype "bidirectional"))
    )
    (net (code "114") (name "/PWM10") (class "Default")
      (node (ref "IC1") (pin "102") (pinfunction "PC29_102") (pintype "bidirectional"))
      (node (ref "J3") (pin "D10") (pinfunction "D10_D10") (pintype "bidirectional"))
    )
    (net (code "115") (name "/PWM11") (class "Default")
      (node (ref "IC1") (pin "20") (pinfunction "PD7_20") (pintype "bidirectional"))
      (node (ref "J3") (pin "D11") (pinfunction "D11_D11") (pintype "bidirectional"))
    )
    (net (code "116") (name "/PWM12") (class "Default")
      (node (ref "IC1") (pin "21") (pinfunction "PD8_21") (pintype "bidirectional"))
      (node (ref "J3") (pin "D12") (pinfunction "D12_D12") (pintype "bidirectional"))
    )
    (net (code "117") (name "/PWM13") (class "Default")
      (node (ref "IC1") (pin "68") (pinfunction "PB27_68") (pintype "bidirectional"))
      (node (ref "J3") (pin "D13") (pinfunction "D13_D13") (pintype "bidirectional"))
    )
    (net (code "118") (name "/PWRGD") (class "Default")
      (node (ref "IC8") (pin "5") (pinfunction "PWRGD_5") (pintype "input"))
      (node (ref "R26") (pin "1") (pinfunction "1_1") (pintype "passive"))
    )
    (net (code "119") (name "/RX") (class "Default")
      (node (ref "IC1") (pin "27") (pinfunction "PA8_27") (pintype "bidirectional"))
      (node (ref "J3") (pin "D0") (pinfunction "D0_D0") (pintype "bidirectional"))
      (node (ref "R32") (pin "2") (pinfunction "2_2") (pintype "passive"))
      (node (ref "R5") (pin "2") (pinfunction "2_2") (pintype "passive"))
    )
    (net (code "120") (name "/RXD0") (class "Default")
      (node (ref "IC1") (pin "18") (pinfunction "PD5_18") (pintype "bidirectional"))
      (node (ref "TP16") (pin "TP") (pinfunction "TP_TP") (pintype "input"))
    )
    (net (code "121") (name "/RXD1") (class "Default")
      (node (ref "IC1") (pin "5") (pinfunction "PA12_5") (pintype "bidirectional"))
      (node (ref "TP12") (pin "TP") (pinfunction "TP_TP") (pintype "input"))
    )
    (net (code "122") (name "/RXD2") (class "Default")
      (node (ref "IC1") (pin "3") (pinfunction "PA10_3") (pintype "bidirectional"))
      (node (ref "TP18") (pin "TP") (pinfunction "TP_TP") (pintype "input"))
    )
    (net (code "123") (name "/RXL") (class "Default")
      (node (ref "IC1") (pin "103") (pinfunction "PC30_103") (pintype "bidirectional"))
      (node (ref "RX") (pin "A") (pinfunction "A_A") (pintype "passive"))
    )
    (net (code "124") (name "/RX_FTDI") (class "Default")
      (node (ref "JP6") (pin "4") (pinfunction "4_4") (pintype "passive"))
      (node (ref "R32") (pin "1") (pinfunction "1_1") (pintype "passive"))
    )
    (net (code "125") (name "/SCK") (class "Default")
      (node (ref "IC1") (pin "110") (pinfunction "PA27_110") (pintype "bidirectional"))
      (node (ref "IC5") (pin "6") (pinfunction "SCK_6") (pintype "bidirectional"))
      (node (ref "J3") (pin "SCK") (pinfunction "SCK_SCK") (pintype "bidirectional"))
      (node (ref "J5") (pin "P5") (pinfunction "SCK_P5") (pintype "bidirectional"))
      (node (ref "J7") (pin "13") (pinfunction "D6_13") (pintype "bidirectional"))
    )
    (net (code "126") (name "/SCL0-3") (class "Default")
      (node (ref "IC1") (pin "87") (pinfunction "PB13_87") (pintype "bidirectional"))
      (node (ref "IC2") (pin "23") (pinfunction "SCL_23") (pintype "bidirectional"))
      (node (ref "R34") (pin "2") (pinfunction "2_2") (pintype "passive"))
    )
    (net (code "127") (name "/SCL1") (class "Default")
      (node (ref "IC1") (pin "70") (pinfunction "PA18_70") (pintype "bidirectional"))
      (node (ref "J3") (pin "SCL") (pinfunction "SCL_SCL") (pintype "bidirectional"))
    )
    (net (code "128") (name "/SCREEN_LEFT") (class "Default")
      (node (ref "IC1") (pin "19") (pinfunction "PD6_19") (pintype "bidirectional"))
      (node (ref "TP20") (pin "TP") (pinfunction "TP_TP") (pintype "input"))
    )
    (net (code "129") (name "/SCREEN_RIGHT") (class "Default")
      (node (ref "IC1") (pin "99") (pinfunction "PC17_99") (pintype "bidirectional"))
      (node (ref "TP21") (pin "TP") (pinfunction "TP_TP") (pintype "input"))
    )
    (net (code "130") (name "/SDA0-3") (class "Default")
      (node (ref "IC1") (pin "86") (pinfunction "PB12_86") (pintype "bidirectional"))
      (node (ref "IC2") (pin "24") (pinfunction "SDA_24") (pintype "bidirectional"))
      (node (ref "R33") (pin "2") (pinfunction "2_2") (pintype "passive"))
    )
    (net (code "131") (name "/SDA1") (class "Default")
      (node (ref "IC1") (pin "9") (pinfunction "PA17_9") (pintype "bidirectional"))
      (node (ref "J3") (pin "SDA") (pinfunction "SDA_SDA") (pintype "bidirectional"))
    )
    (net (code "132") (name "/SD_CARD_DECTECT") (class "Default")
      (node (ref "IC1") (pin "116") (pinfunction "PC4_116") (pintype "bidirectional"))
      (node (ref "J5") (pin "G1") (pinfunction "SHIELD_G1") (pintype "bidirectional"))
    )
    (net (code "133") (name "/SD_CS") (class "Default")
      (node (ref "IC1") (pin "112") (pinfunction "PA29_112") (pintype "bidirectional"))
      (node (ref "J5") (pin "P2") (pinfunction "CS_P2") (pintype "bidirectional"))
    )
    (net (code "134") (name "/SETC") (class "Default")
      (node (ref "C31") (pin "1") (pinfunction "1_1") (pintype "passive"))
      (node (ref "IC7") (pin "12") (pinfunction "SETC_12") (pintype "bidirectional"))
    )
    (net (code "135") (name "/SHDN") (class "Default")
      (node (ref "IC1") (pin "50") (pinfunction "SHDN_50") (pintype "output"))
      (node (ref "IC8") (pin "1") (pinfunction "~{SHDN}_1") (pintype "input"))
    )
    (net (code "136") (name "/SRF_P0_1{slash}MODE_PIN_1") (class "Default")
      (node (ref "IC3") (pin "17") (pinfunction "P0_1_17") (pintype "bidirectional"))
      (node (ref "JP8") (pin "6") (pinfunction "6_6") (pintype "passive"))
    )
    (net (code "137") (name "/SRF_P0_2{slash}RX") (class "Default")
      (node (ref "IC3") (pin "2") (pinfunction "P0_2/RX_2") (pintype "bidirectional"))
      (node (ref "JP8") (pin "8") (pinfunction "8_8") (pintype "passive"))
      (node (ref "R6") (pin "1") (pinfunction "1_1") (pintype "passive"))
    )
    (net (code "138") (name "/SRF_P0_3{slash}TX") (class "Default")
      (node (ref "IC3") (pin "3") (pinfunction "P0_3/TX_3") (pintype "bidirectional"))
      (node (ref "JP8") (pin "7") (pinfunction "7_7") (pintype "passive"))
      (node (ref "R5") (pin "1") (pinfunction "1_1") (pintype "passive"))
    )
    (net (code "139") (name "/SRF_P1_4{slash}SLEEP") (class "Default")
      (node (ref "IC1") (pin "85") (pinfunction "PA2_85") (pintype "bidirectional"))
      (node (ref "IC3") (pin "14") (pinfunction "P1_4/SS_14") (pintype "bidirectional"))
    )
    (net (code "140") (name "/SRF_P2_0{slash}AT_COMMAND") (class "Default")
      (node (ref "IC1") (pin "72") (pinfunction "PA20_72") (pintype "bidirectional"))
      (node (ref "IC3") (pin "4") (pinfunction "P2_0_4") (pintype "bidirectional"))
    )
    (net (code "141") (name "/SRF_P2_1{slash}DD") (class "Default")
      (node (ref "IC3") (pin "5") (pinfunction "P2_1/DD_5") (pintype "bidirectional"))
      (node (ref "JP8") (pin "4") (pinfunction "4_4") (pintype "passive"))
    )
    (net (code "142") (name "/SRF_P2_2{slash}DC") (class "Default")
      (node (ref "IC3") (pin "6") (pinfunction "P2_2/DC_6") (pintype "bidirectional"))
      (node (ref "JP8") (pin "3") (pinfunction "3_3") (pintype "passive"))
      (node (ref "SJ1") (pin "1") (pinfunction "1_1") (pintype "passive"))
    )
    (net (code "143") (name "/SRF_P2_3") (class "Default")
      (node (ref "IC3") (pin "7") (pinfunction "P2_3_7") (pintype "bidirectional"))
      (node (ref "SJ2") (pin "1") (pinfunction "1_1") (pintype "passive"))
    )
    (net (code "144") (name "/SRF_~{RESET}") (class "Default")
      (node (ref "IC3") (pin "15") (pinfunction "~{RESET}_15") (pintype "input"))
      (node (ref "JP8") (pin "5") (pinfunction "5_5") (pintype "passive"))
    )
    (net (code "145") (name "/SS3") (class "Default")
      (node (ref "IC1") (pin "142") (pinfunction "PB23_142") (pintype "bidirectional"))
      (node (ref "TP6") (pin "TP") (pinfunction "TP_TP") (pintype "input"))
    )
    (net (code "146") (name "/STEP") (class "Default")
      (node (ref "C31") (pin "2") (pinfunction "2_2") (pintype "passive"))
      (node (ref "IC7") (pin "8") (pinfunction "SETP_8") (pintype "bidirectional"))
    )
    (net (code "147") (name "/TX") (class "Default")
      (node (ref "IC1") (pin "2") (pinfunction "PA9_2") (pintype "bidirectional"))
      (node (ref "J3") (pin "D1") (pinfunction "D1_D1") (pintype "bidirectional"))
      (node (ref "R31") (pin "2") (pinfunction "2_2") (pintype "passive"))
      (node (ref "R6") (pin "2") (pinfunction "2_2") (pintype "passive"))
    )
    (net (code "148") (name "/TXD0") (class "Default")
      (node (ref "IC1") (pin "17") (pinfunction "PD4_17") (pintype "bidirectional"))
      (node (ref "TP15") (pin "TP") (pinfunction "TP_TP") (pintype "input"))
    )
    (net (code "149") (name "/TXD1") (class "Default")
      (node (ref "IC1") (pin "6") (pinfunction "PA13_6") (pintype "bidirectional"))
      (node (ref "TP11") (pin "TP") (pinfunction "TP_TP") (pintype "input"))
    )
    (net (code "150") (name "/TXD2") (class "Default")
      (node (ref "IC1") (pin "4") (pinfunction "PA11_4") (pintype "bidirectional"))
      (node (ref "TP17") (pin "TP") (pinfunction "TP_TP") (pintype "input"))
    )
    (net (code "151") (name "/TXL") (class "Default")
      (node (ref "IC1") (pin "107") (pinfunction "PA21_107") (pintype "bidirectional"))
      (node (ref "TX") (pin "A") (pinfunction "A_A") (pintype "passive"))
    )
    (net (code "152") (name "/TX_FTDI") (class "Default")
      (node (ref "JP6") (pin "5") (pinfunction "5_5") (pintype "passive"))
      (node (ref "R31") (pin "1") (pinfunction "1_1") (pintype "passive"))
    )
    (net (code "153") (name "/UOTGID") (class "Default")
      (node (ref "IC1") (pin "129") (pinfunction "PB11_129") (pintype "bidirectional"))
      (node (ref "J1") (pin "ID") (pinfunction "USBID_ID") (pintype "bidirectional"))
      (node (ref "Z3") (pin "1") (pinfunction "1_1") (pintype "passive"))
    )
    (net (code "154") (name "/UOTGVBOF") (class "Default")
      (node (ref "IC1") (pin "128") (pinfunction "PB10_128") (pintype "bidirectional"))
      (node (ref "TP27") (pin "TP") (pinfunction "TP_TP") (pintype "input"))
    )
    (net (code "155") (name "/VBACKUP") (class "Default")
      (node (ref "C120") (pin "1") (pinfunction "1_1") (pintype "passive"))
      (node (ref "C27") (pin "2") (pinfunction "2_2") (pintype "passive"))
      (node (ref "C34") (pin "2") (pinfunction "2_2") (pintype "passive"))
      (node (ref "C4") (pin "1") (pinfunction "1_1") (pintype "passive"))
      (node (ref "C50") (pin "+") (pinfunction "+_+") (pintype "passive"))
      (node (ref "C8") (pin "2") (pinfunction "2_2") (pintype "passive"))
      (node (ref "C9") (pin "2") (pinfunction "2_2") (pintype "passive"))
      (node (ref "D2") (pin "1") (pinfunction "A1_1") (pintype "passive"))
      (node (ref "IC1") (pin "52") (pinfunction "VDDBU_52") (pintype "power_in"))
      (node (ref "IC2") (pin "13") (pinfunction "VDD_13") (pintype "bidirectional"))
      (node (ref "IC2") (pin "8") (pinfunction "VLOGIC_8") (pintype "bidirectional"))
      (node (ref "IC7") (pin "13") (pinfunction "VDDIO_13") (pintype "bidirectional"))
      (node (ref "IC7") (pin "2") (pinfunction "VDD_2") (pintype "bidirectional"))
      (node (ref "IC7") (pin "4") (pinfunction "S1_4") (pintype "bidirectional"))
      (node (ref "IC9") (pin "5") (pinfunction "OUT_5") (pintype "passive"))
      (node (ref "JP1") (pin "2") (pinfunction "2_2") (pintype "passive"))
      (node (ref "Q8") (pin "2") (pinfunction "S_2") (pintype "bidirectional"))
      (node (ref "R104") (pin "2") (pinfunction "2_2") (pintype "passive"))
      (node (ref "R33") (pin "1") (pinfunction "1_1") (pintype "passive"))
      (node (ref "R34") (pin "1") (pinfunction "1_1") (pintype "passive"))
      (node (ref "R41") (pin "2") (pinfunction "2_2") (pintype "passive"))
      (node (ref "SJ10") (pin "3") (pinfunction "3_3") (pintype "passive"))
    )
    (net (code "156") (name "/VBATT") (class "Default")
      (node (ref "C48") (pin "2") (pinfunction "2_2") (pintype "passive"))
      (node (ref "IC10") (pin "3") (pinfunction "VBAT_3") (pintype "power_in"))
      (node (ref "J8") (pin "2") (pinfunction "2_2") (pintype "passive"))
      (node (ref "Q14") (pin "3") (pinfunction "D_3") (pintype "bidirectional"))
    )
    (net (code "157") (name "/VBATT_MON") (class "Default")
      (node (ref "IC1") (pin "91") (pinfunction "PB20_91") (pintype "bidirectional"))
      (node (ref "R38") (pin "1") (pinfunction "1_1") (pintype "passive"))
      (node (ref "R39") (pin "1") (pinfunction "1_1") (pintype "passive"))
    )
    (net (code "158") (name "/VBATT_PROTECTED") (class "Default")
      (node (ref "Q14") (pin "2") (pinfunction "S_2") (pintype "bidirectional"))
      (node (ref "S8") (pin "3") (pinfunction "S_3") (pintype "passive"))
    )
    (net (code "159") (name "/VBATT_SWITCHED") (class "Default")
      (node (ref "C36") (pin "2") (pinfunction "2_2") (pintype "passive"))
      (node (ref "IC8") (pin "2") (pinfunction "VIN_2") (pintype "input"))
      (node (ref "IC9") (pin "1") (pinfunction "IN_1") (pintype "input"))
      (node (ref "IC9") (pin "3") (pinfunction "EN_3") (pintype "input"))
      (node (ref "R38") (pin "2") (pinfunction "2_2") (pintype "passive"))
      (node (ref "S8") (pin "2") (pinfunction "P_2") (pintype "passive"))
    )
    (net (code "160") (name "/VBG") (class "Default")
      (node (ref "C125") (pin "2") (pinfunction "2_2") (pintype "passive"))
      (node (ref "IC1") (pin "40") (pinfunction "VBG_40") (pintype "passive"))
      (node (ref "R107") (pin "1") (pinfunction "1_1") (pintype "passive"))
    )
    (net (code "161") (name "/VBUS") (class "Default")
      (node (ref "C126") (pin "1") (pinfunction "1_1") (pintype "passive"))
      (node (ref "C127") (pin "+") (pinfunction "+_+") (pintype "passive"))
      (node (ref "C135") (pin "+") (pinfunction "+_+") (pintype "passive"))
      (node (ref "C33") (pin "2") (pinfunction "2_2") (pintype "passive"))
      (node (ref "C49") (pin "2") (pinfunction "2_2") (pintype "passive"))
      (node (ref "IC1") (pin "39") (pinfunction "VBUS_39") (pintype "power_in"))
      (node (ref "IC10") (pin "4") (pinfunction "VIN_4") (pintype "power_in"))
      (node (ref "J1") (pin "VBUS") (pinfunction "VBUS_VBUS") (pintype "bidirectional"))
      (node (ref "JP9") (pin "1") (pinfunction "1_1") (pintype "passive"))
      (node (ref "R102") (pin "2") (pinfunction "2_2") (pintype "passive"))
      (node (ref "S8") (pin "1") (pinfunction "O_1") (pintype "passive"))
    )
    (net (code "162") (name "/VDDANA") (class "Default")
      (node (ref "C103") (pin "+") (pinfunction "+_+") (pintype "passive"))
      (node (ref "C110") (pin "2") (pinfunction "2_2") (pintype "passive"))
      (node (ref "IC1") (pin "73") (pinfunction "VDDANA_73") (pintype "power_in"))
      (node (ref "L101") (pin "2") (pinfunction "2_2") (pintype "passive"))
    )
    (net (code "163") (name "/VDDIO") (class "Default")
      (node (ref "C101") (pin "+") (pinfunction "+_+") (pintype "passive"))
      (node (ref "C104") (pin "2") (pinfunction "2_2") (pintype "passive"))
      (node (ref "C105") (pin "2") (pinfunction "2_2") (pintype "passive"))
      (node (ref "C107") (pin "2") (pinfunction "2_2") (pintype "passive"))
      (node (ref "C108") (pin "2") (pinfunction "2_2") (pintype "passive"))
      (node (ref "C118") (pin "2") (pinfunction "2_2") (pintype "passive"))
      (node (ref "D2") (pin "3") (pinfunction "CC_3") (pintype "passive"))
      (node (ref "IC1") (pin "105") (pinfunction "VDDIO3_105") (pintype "power_in"))
      (node (ref "IC1") (pin "11") (pinfunction "VDDIO1_11") (pintype "power_in"))
      (node (ref "IC1") (pin "125") (pinfunction "VDDIO4_125") (pintype "power_in"))
      (node (ref "IC1") (pin "62") (pinfunction "VDDIO2_62") (pintype "power_in"))
      (node (ref "L101") (pin "1") (pinfunction "1_1") (pintype "passive"))
      (node (ref "L102") (pin "1") (pinfunction "1_1") (pintype "passive"))
      (node (ref "R21") (pin "2") (pinfunction "2_2") (pintype "passive"))
      (node (ref "R22") (pin "2") (pinfunction "2_2") (pintype "passive"))
      (node (ref "R23") (pin "2") (pinfunction "2_2") (pintype "passive"))
      (node (ref "R24") (pin "2") (pinfunction "2_2") (pintype "passive"))
      (node (ref "R44") (pin "2") (pinfunction "2_2") (pintype "passive"))
      (node (ref "R47") (pin "2") (pinfunction "2_2") (pintype "passive"))
      (node (ref "R48") (pin "2") (pinfunction "2_2") (pintype "passive"))
      (node (ref "R49") (pin "1") (pinfunction "1_1") (pintype "passive"))
      (node (ref "SJ10") (pin "2") (pinfunction "2_2") (pintype "passive"))
      (node (ref "SJ8") (pin "3") (pinfunction "3_3") (pintype "passive"))
    )
    (net (code "164") (name "/VDDOUT") (class "Default")
      (node (ref "C111") (pin "+") (pinfunction "+_+") (pintype "passive"))
      (node (ref "C112") (pin "2") (pinfunction "2_2") (pintype "passive"))
      (node (ref "C113") (pin "2") (pinfunction "2_2") (pintype "passive"))
      (node (ref "C114") (pin "2") (pinfunction "2_2") (pintype "passive"))
      (node (ref "C115") (pin "2") (pinfunction "2_2") (pintype "passive"))
      (node (ref "C116") (pin "2") (pinfunction "2_2") (pintype "passive"))
      (node (ref "C117") (pin "2") (pinfunction "2_2") (pintype "passive"))
      (node (ref "IC1") (pin "10") (pinfunction "VDDCORE1_10") (pintype "input"))
      (node (ref "IC1") (pin "104") (pinfunction "VDDCORE4_104") (pintype "input"))
      (node (ref "IC1") (pin "124") (pinfunction "VDDCORE5_124") (pintype "input"))
      (node (ref "IC1") (pin "45") (pinfunction "VDDCORE2_45") (pintype "input"))
      (node (ref "IC1") (pin "56") (pinfunction "VDDOUT_56") (pintype "output"))
      (node (ref "IC1") (pin "61") (pinfunction "VDDCORE3_61") (pintype "input"))
      (node (ref "L105") (pin "1") (pinfunction "1_1") (pintype "passive"))
    )
    (net (code "165") (name "/VDDOUTIMI") (class "Default")
      (node (ref "C102") (pin "+") (pinfunction "+_+") (pintype "passive"))
      (node (ref "C109") (pin "2") (pinfunction "2_2") (pintype "passive"))
      (node (ref "IC1") (pin "41") (pinfunction "VDDUTMI_41") (pintype "input"))
      (node (ref "L102") (pin "2") (pinfunction "2_2") (pintype "passive"))
    )
    (net (code "166") (name "/VDDPLL") (class "Default")
      (node (ref "C132") (pin "1") (pinfunction "1_1") (pintype "passive"))
      (node (ref "C133") (pin "+") (pinfunction "+_+") (pintype "passive"))
      (node (ref "IC1") (pin "34") (pinfunction "VDDPLL_34") (pintype "input"))
      (node (ref "L105") (pin "2") (pinfunction "2_2") (pintype "passive"))
    )
    (net (code "167") (name "/VIN") (class "Default")
      (node (ref "J3") (pin "VIN") (pinfunction "VIN_VIN") (pintype "power_in"))
    )
    (net (code "168") (name "/XIN") (class "Default")
      (node (ref "C122") (pin "2") (pinfunction "2_2") (pintype "passive"))
      (node (ref "IC1") (pin "36") (pinfunction "XIN_36") (pintype "input"))
      (node (ref "X1") (pin "1") (pinfunction "C1_1") (pintype "passive"))
    )
    (net (code "169") (name "/XIN32") (class "Default")
      (node (ref "C124") (pin "2") (pinfunction "2_2") (pintype "passive"))
      (node (ref "IC1") (pin "48") (pinfunction "XIN32_48") (pintype "output"))
      (node (ref "X2") (pin "P$1") (pinfunction "1_P$1") (pintype "bidirectional"))
    )
    (net (code "170") (name "/XOUT") (class "Default")
      (node (ref "C121") (pin "2") (pinfunction "2_2") (pintype "passive"))
      (node (ref "IC1") (pin "35") (pinfunction "XOUT_35") (pintype "output"))
      (node (ref "X1") (pin "3") (pinfunction "C2_3") (pintype "passive"))
    )
    (net (code "171") (name "/XOUT32") (class "Default")
      (node (ref "C123") (pin "2") (pinfunction "2_2") (pintype "passive"))
      (node (ref "IC1") (pin "49") (pinfunction "XOUT32_49") (pintype "output"))
      (node (ref "X2") (pin "P$2") (pinfunction "2_P$2") (pintype "bidirectional"))
    )
    (net (code "172") (name "GND") (class "Default")
      (node (ref "C101") (pin "-") (pinfunction "-_-") (pintype "passive"))
      (node (ref "C102") (pin "-") (pinfunction "-_-") (pintype "passive"))
      (node (ref "C103") (pin "-") (pinfunction "-_-") (pintype "passive"))
      (node (ref "C104") (pin "1") (pinfunction "1_1") (pintype "passive"))
      (node (ref "C105") (pin "1") (pinfunction "1_1") (pintype "passive"))
      (node (ref "C106") (pin "1") (pinfunction "1_1") (pintype "passive"))
      (node (ref "C107") (pin "1") (pinfunction "1_1") (pintype "passive"))
      (node (ref "C108") (pin "1") (pinfunction "1_1") (pintype "passive"))
      (node (ref "C109") (pin "1") (pinfunction "1_1") (pintype "passive"))
      (node (ref "C110") (pin "1") (pinfunction "1_1") (pintype "passive"))
      (node (ref "C111") (pin "-") (pinfunction "-_-") (pintype "passive"))
      (node (ref "C112") (pin "1") (pinfunction "1_1") (pintype "passive"))
      (node (ref "C113") (pin "1") (pinfunction "1_1") (pintype "passive"))
      (node (ref "C114") (pin "1") (pinfunction "1_1") (pintype "passive"))
      (node (ref "C115") (pin "1") (pinfunction "1_1") (pintype "passive"))
      (node (ref "C116") (pin "1") (pinfunction "1_1") (pintype "passive"))
      (node (ref "C117") (pin "1") (pinfunction "1_1") (pintype "passive"))
      (node (ref "C118") (pin "1") (pinfunction "1_1") (pintype "passive"))
      (node (ref "C119") (pin "1") (pinfunction "1_1") (pintype "passive"))
      (node (ref "C121") (pin "1") (pinfunction "1_1") (pintype "passive"))
      (node (ref "C122") (pin "1") (pinfunction "1_1") (pintype "passive"))
      (node (ref "C123") (pin "1") (pinfunction "1_1") (pintype "passive"))
      (node (ref "C124") (pin "1") (pinfunction "1_1") (pintype "passive"))
      (node (ref "C125") (pin "1") (pinfunction "1_1") (pintype "passive"))
      (node (ref "C126") (pin "2") (pinfunction "2_2") (pintype "passive"))
      (node (ref "C127") (pin "-") (pinfunction "-_-") (pintype "passive"))
      (node (ref "C132") (pin "2") (pinfunction "2_2") (pintype "passive"))
      (node (ref "C133") (pin "-") (pinfunction "-_-") (pintype "passive"))
      (node (ref "C134") (pin "1") (pinfunction "1_1") (pintype "passive"))
      (node (ref "C135") (pin "-") (pinfunction "-_-") (pintype "passive"))
      (node (ref "C2") (pin "1") (pinfunction "1_1") (pintype "passive"))
      (node (ref "C27") (pin "1") (pinfunction "1_1") (pintype "passive"))
      (node (ref "C28") (pin "1") (pinfunction "1_1") (pintype "passive"))
      (node (ref "C30") (pin "2") (pinfunction "2_2") (pintype "passive"))
      (node (ref "C32") (pin "1") (pinfunction "1_1") (pintype "passive"))
      (node (ref "C33") (pin "1") (pinfunction "1_1") (pintype "passive"))
      (node (ref "C34") (pin "1") (pinfunction "1_1") (pintype "passive"))
      (node (ref "C36") (pin "1") (pinfunction "1_1") (pintype "passive"))
      (node (ref "C37") (pin "2") (pinfunction "2_2") (pintype "passive"))
      (node (ref "C38") (pin "1") (pinfunction "1_1") (pintype "passive"))
      (node (ref "C39") (pin "1") (pinfunction "1_1") (pintype "passive"))
      (node (ref "C4") (pin "2") (pinfunction "2_2") (pintype "passive"))
      (node (ref "C43") (pin "1") (pinfunction "1_1") (pintype "passive"))
      (node (ref "C44") (pin "1") (pinfunction "1_1") (pintype "passive"))
      (node (ref "C45") (pin "1") (pinfunction "1_1") (pintype "passive"))
      (node (ref "C46") (pin "1") (pinfunction "1_1") (pintype "passive"))
      (node (ref "C47") (pin "1") (pinfunction "1_1") (pintype "passive"))
      (node (ref "C48") (pin "1") (pinfunction "1_1") (pintype "passive"))
      (node (ref "C49") (pin "1") (pinfunction "1_1") (pintype "passive"))
      (node (ref "C5") (pin "2") (pinfunction "2_2") (pintype "passive"))
      (node (ref "C50") (pin "-") (pinfunction "-_-") (pintype "passive"))
      (node (ref "C6") (pin "2") (pinfunction "2_2") (pintype "passive"))
      (node (ref "C8") (pin "1") (pinfunction "1_1") (pintype "passive"))
      (node (ref "C9") (pin "1") (pinfunction "1_1") (pintype "passive"))
      (node (ref "IC1") (pin "106") (pinfunction "GND3_106") (pintype "power_in"))
      (node (ref "IC1") (pin "12") (pinfunction "GND1_12") (pintype "power_in"))
      (node (ref "IC1") (pin "126") (pinfunction "GND4_126") (pintype "power_in"))
      (node (ref "IC1") (pin "33") (pinfunction "GNDPLL_33") (pintype "power_in"))
      (node (ref "IC1") (pin "44") (pinfunction "GNDUTMI_44") (pintype "power_in"))
      (node (ref "IC1") (pin "46") (pinfunction "JTAGSEL_46") (pintype "input"))
      (node (ref "IC1") (pin "54") (pinfunction "GNDBU_54") (pintype "power_in"))
      (node (ref "IC1") (pin "58") (pinfunction "GND2_58") (pintype "power_in"))
      (node (ref "IC1") (pin "74") (pinfunction "GNDANA_74") (pintype "power_in"))
      (node (ref "IC10") (pin "2") (pinfunction "VSS_2") (pintype "power_in"))
      (node (ref "IC2") (pin "1") (pinfunction "CLKIN_1") (pintype "bidirectional"))
      (node (ref "IC2") (pin "11") (pinfunction "FSYNC_11") (pintype "bidirectional"))
      (node (ref "IC2") (pin "18") (pinfunction "GND_18") (pintype "bidirectional"))
      (node (ref "IC2") (pin "9") (pinfunction "AD0_9") (pintype "bidirectional"))
      (node (ref "IC3") (pin "10") (pinfunction "GND_10") (pintype "power_in"))
      (node (ref "IC5") (pin "4") (pinfunction "GND_4") (pintype "bidirectional"))
      (node (ref "IC7") (pin "11") (pinfunction "GND_11") (pintype "bidirectional"))
      (node (ref "IC7") (pin "9") (pinfunction "GND_9") (pintype "bidirectional"))
      (node (ref "IC8") (pin "3") (pinfunction "GND_3") (pintype "passive"))
      (node (ref "IC8") (pin "6") (pinfunction "GND_6") (pintype "passive"))
      (node (ref "IC9") (pin "2") (pinfunction "GND_2") (pintype "input"))
      (node (ref "IR_RX") (pin "1") (pinfunction "GND_1") (pintype "bidirectional"))
      (node (ref "IR_RX") (pin "4") (pinfunction "NC/GND_4") (pintype "bidirectional"))
      (node (ref "J1") (pin "GND") (pinfunction "GND_GND") (pintype "bidirectional"))
      (node (ref "J1") (pin "P$1") (pinfunction "GND_P$1") (pintype "bidirectional"))
      (node (ref "J1") (pin "P$2") (pinfunction "GND_P$2") (pintype "bidirectional"))
      (node (ref "J1") (pin "P$6") (pinfunction "GND_P$6") (pintype "bidirectional"))
      (node (ref "J1") (pin "P$7") (pinfunction "GND_P$7") (pintype "bidirectional"))
      (node (ref "J1") (pin "P$8") (pinfunction "GND_P$8") (pintype "bidirectional"))
      (node (ref "J1") (pin "P$9") (pinfunction "GND_P$9") (pintype "bidirectional"))
      (node (ref "J3") (pin "GND@1") (pinfunction "GND_GND@1") (pintype "power_in"))
      (node (ref "J3") (pin "GND@2") (pinfunction "GND_GND@2") (pintype "power_in"))
      (node (ref "J3") (pin "GND@3") (pinfunction "GND_GND@3") (pintype "power_in"))
      (node (ref "J3") (pin "GND@ISP") (pinfunction "GND_GND@ISP") (pintype "power_in"))
      (node (ref "J5") (pin "P6") (pinfunction "GND_P6") (pintype "bidirectional"))
      (node (ref "J5") (pin "PAD@1") (pinfunction "SHIELD_PAD@1") (pintype "bidirectional"))
      (node (ref "J5") (pin "PAD@2") (pinfunction "SHIELD_PAD@2") (pintype "bidirectional"))
      (node (ref "J5") (pin "PAD@3") (pinfunction "SHIELD_PAD@3") (pintype "bidirectional"))
      (node (ref "J5") (pin "PAD@4") (pinfunction "SHIELD_PAD@4") (pintype "bidirectional"))
      (node (ref "J6") (pin "2") (pinfunction "GND_2") (pintype "bidirectional"))
      (node (ref "J7") (pin "16") (pinfunction "VSS_16") (pintype "bidirectional"))
      (node (ref "J7") (pin "29") (pinfunction "PS_29") (pintype "bidirectional"))
      (node (ref "J7") (pin "M1") (pinfunction "VSS_M1") (pintype "bidirectional"))
      (node (ref "J7") (pin "M2") (pinfunction "VSS_M2") (pintype "bidirectional"))
      (node (ref "J8") (pin "1") (pinfunction "1_1") (pintype "passive"))
      (node (ref "JP2") (pin "3") (pinfunction "3_3") (pintype "passive"))
      (node (ref "JP2") (pin "5") (pinfunction "5_5") (pintype "passive"))
      (node (ref "JP2") (pin "9") (pinfunction "9_9") (pintype "passive"))
      (node (ref "JP6") (pin "1") (pinfunction "1_1") (pintype "passive"))
      (node (ref "JP6") (pin "2") (pinfunction "2_2") (pintype "passive"))
      (node (ref "JP7") (pin "15") (pinfunction "15_15") (pintype "passive"))
      (node (ref "JP7") (pin "16") (pinfunction "16_16") (pintype "passive"))
      (node (ref "JP8") (pin "1") (pinfunction "1_1") (pintype "passive"))
      (node (ref "Q10") (pin "2") (pinfunction "S_2") (pintype "bidirectional"))
      (node (ref "Q12") (pin "2") (pinfunction "S_2") (pintype "bidirectional"))
      (node (ref "Q14") (pin "1") (pinfunction "G_1") (pintype "bidirectional"))
      (node (ref "Q9") (pin "2") (pinfunction "S_2") (pintype "bidirectional"))
      (node (ref "R102") (pin "1") (pinfunction "1_1") (pintype "passive"))
      (node (ref "R107") (pin "2") (pinfunction "2_2") (pintype "passive"))
      (node (ref "R108") (pin "1") (pinfunction "1_1") (pintype "passive"))
      (node (ref "R14") (pin "2") (pinfunction "2_2") (pintype "passive"))
      (node (ref "R39") (pin "2") (pinfunction "2_2") (pintype "passive"))
      (node (ref "R40") (pin "2") (pinfunction "2_2") (pintype "passive"))
      (node (ref "R42") (pin "2") (pinfunction "2_2") (pintype "passive"))
      (node (ref "R43") (pin "2") (pinfunction "2_2") (pintype "passive"))
      (node (ref "R46") (pin "2") (pinfunction "2_2") (pintype "passive"))
      (node (ref "R8") (pin "2") (pinfunction "2_2") (pintype "passive"))
      (node (ref "S1") (pin "3") (pinfunction "3_3") (pintype "passive"))
      (node (ref "S1") (pin "4") (pinfunction "4_4") (pintype "passive"))
      (node (ref "S10") (pin "2") (pinfunction "3_2") (pintype "passive"))
      (node (ref "S4") (pin "3") (pinfunction "3_3") (pintype "passive"))
      (node (ref "S4") (pin "4") (pinfunction "4_4") (pintype "passive"))
      (node (ref "S5") (pin "3") (pinfunction "3_3") (pintype "passive"))
      (node (ref "S5") (pin "4") (pinfunction "4_4") (pintype "passive"))
      (node (ref "S6") (pin "1") (pinfunction "1_1") (pintype "passive"))
      (node (ref "S6") (pin "2") (pinfunction "2_2") (pintype "passive"))
      (node (ref "S7") (pin "GND") (pinfunction "GND_GND") (pintype "bidirectional"))
      (node (ref "S9") (pin "2") (pinfunction "3_2") (pintype "passive"))
      (node (ref "SG1") (pin "P$2") (pinfunction "2_P$2") (pintype "passive"))
      (node (ref "TP1") (pin "TP") (pinfunction "TP_TP") (pintype "input"))
      (node (ref "X1") (pin "2") (pinfunction "GND_2") (pintype "passive"))
      (node (ref "X1") (pin "4") (pinfunction "GND_4") (pintype "passive"))
      (node (ref "Z1") (pin "2") (pinfunction "2_2") (pintype "passive"))
      (node (ref "Z2") (pin "2") (pinfunction "2_2") (pintype "passive"))
      (node (ref "Z3") (pin "2") (pinfunction "2_2") (pintype "passive"))
    )
    (net (code "173") (name "Net-(C134-Pad2)") (class "Default")
      (node (ref "C134") (pin "2") (pinfunction "2_2") (pintype "passive"))
      (node (ref "L103") (pin "1") (pinfunction "1_1") (pintype "passive"))
      (node (ref "SJ8") (pin "2") (pinfunction "2_2") (pintype "passive"))
    )
    (net (code "174") (name "Net-(IC1-FWUP)") (class "Default")
      (node (ref "IC1") (pin "53") (pinfunction "FWUP_53") (pintype "input"))
      (node (ref "R104") (pin "1") (pinfunction "1_1") (pintype "passive"))
    )
    (net (code "175") (name "Net-(IC1-TST)") (class "Default")
      (node (ref "IC1") (pin "51") (pinfunction "TST_51") (pintype "input"))
      (node (ref "R108") (pin "2") (pinfunction "2_2") (pintype "passive"))
    )
    (net (code "176") (name "Net-(IC3-P1_5{slash}SCK)") (class "Default")
      (node (ref "IC3") (pin "13") (pinfunction "P1_5/SCK_13") (pintype "bidirectional"))
      (node (ref "TP3") (pin "TP") (pinfunction "TP_TP") (pintype "input"))
    )
    (net (code "177") (name "Net-(IC3-P1_6{slash}MOSI)") (class "Default")
      (node (ref "IC3") (pin "12") (pinfunction "P1_6/MOSI_12") (pintype "bidirectional"))
      (node (ref "TP2") (pin "TP") (pinfunction "TP_TP") (pintype "input"))
    )
    (net (code "178") (name "Net-(IR_RX-VS)") (class "Default")
      (node (ref "IR_RX") (pin "2") (pinfunction "VS_2") (pintype "bidirectional"))
      (node (ref "Q13") (pin "3") (pinfunction "D_3") (pintype "bidirectional"))
    )
    (net (code "179") (name "Net-(IR_TX-PadA)") (class "Default")
      (node (ref "IR_TX") (pin "A") (pinfunction "A_A") (pintype "passive"))
      (node (ref "R4") (pin "1") (pinfunction "1_1") (pintype "passive"))
    )
    (net (code "180") (name "Net-(J7-D0)") (class "Default")
      (node (ref "J7") (pin "10") (pinfunction "D3_10") (pintype "bidirectional"))
      (node (ref "J7") (pin "11") (pinfunction "D4_11") (pintype "bidirectional"))
      (node (ref "J7") (pin "12") (pinfunction "D5_12") (pintype "bidirectional"))
      (node (ref "J7") (pin "7") (pinfunction "D0_7") (pintype "bidirectional"))
      (node (ref "J7") (pin "8") (pinfunction "D1_8") (pintype "bidirectional"))
      (node (ref "J7") (pin "9") (pinfunction "D2_9") (pintype "bidirectional"))
      (node (ref "SJ11") (pin "2") (pinfunction "2_2") (pintype "passive"))
    )
    (net (code "181") (name "Net-(LED1-CBLUE)") (class "Default")
      (node (ref "LED1") (pin "B") (pinfunction "CBLUE_B") (pintype "passive"))
      (node (ref "R18") (pin "1") (pinfunction "1_1") (pintype "passive"))
    )
    (net (code "182") (name "Net-(LED1-CGREEN)") (class "Default")
      (node (ref "LED1") (pin "G") (pinfunction "CGREEN_G") (pintype "passive"))
      (node (ref "R19") (pin "1") (pinfunction "1_1") (pintype "passive"))
    )
    (net (code "183") (name "Net-(LED1-CRED)") (class "Default")
      (node (ref "LED1") (pin "R") (pinfunction "CRED_R") (pintype "passive"))
      (node (ref "R20") (pin "1") (pinfunction "1_1") (pintype "passive"))
    )
    (net (code "184") (name "Net-(LED2-CBLUE)") (class "Default")
      (node (ref "LED2") (pin "B") (pinfunction "CBLUE_B") (pintype "passive"))
      (node (ref "R15") (pin "1") (pinfunction "1_1") (pintype "passive"))
    )
    (net (code "185") (name "Net-(LED2-CGREEN)") (class "Default")
      (node (ref "LED2") (pin "G") (pinfunction "CGREEN_G") (pintype "passive"))
      (node (ref "R16") (pin "1") (pinfunction "1_1") (pintype "passive"))
    )
    (net (code "186") (name "Net-(LED2-CRED)") (class "Default")
      (node (ref "LED2") (pin "R") (pinfunction "CRED_R") (pintype "passive"))
      (node (ref "R17") (pin "1") (pinfunction "1_1") (pintype "passive"))
    )
    (net (code "187") (name "Net-(Q9-D)") (class "Default")
      (node (ref "IR_TX") (pin "C") (pinfunction "C_C") (pintype "passive"))
      (node (ref "Q9") (pin "3") (pinfunction "D_3") (pintype "bidirectional"))
    )
    (net (code "188") (name "Net-(Q12-D)") (class "Default")
      (node (ref "Q12") (pin "3") (pinfunction "D_3") (pintype "bidirectional"))
      (node (ref "R45") (pin "2") (pinfunction "2_2") (pintype "passive"))
    )
    (net (code "189") (name "Net-(R8-Pad1)") (class "Default")
      (node (ref "R8") (pin "1") (pinfunction "1_1") (pintype "passive"))
      (node (ref "TX") (pin "C") (pinfunction "C_C") (pintype "passive"))
    )
    (net (code "190") (name "Net-(R14-Pad1)") (class "Default")
      (node (ref "R14") (pin "1") (pinfunction "1_1") (pintype "passive"))
      (node (ref "RX") (pin "C") (pinfunction "C_C") (pintype "passive"))
    )
    (net (code "191") (name "Net-(R25-Pad2)") (class "Default")
      (node (ref "R25") (pin "2") (pinfunction "2_2") (pintype "passive"))
      (node (ref "SJ7") (pin "1") (pinfunction "1_1") (pintype "passive"))
    )
    (net (code "192") (name "Net-(R45-Pad1)") (class "Default")
      (node (ref "R45") (pin "1") (pinfunction "1_1") (pintype "passive"))
      (node (ref "U2") (pin "K") (pinfunction "K_K") (pintype "bidirectional"))
    )
    (net (code "193") (name "Net-(S4-Pad1)") (class "Default")
      (node (ref "S4") (pin "1") (pinfunction "1_1") (pintype "passive"))
      (node (ref "S4") (pin "2") (pinfunction "2_2") (pintype "passive"))
      (node (ref "SJ6") (pin "2") (pinfunction "2_2") (pintype "passive"))
    )
    (net (code "194") (name "Net-(SG1-1)") (class "Default")
      (node (ref "R25") (pin "1") (pinfunction "1_1") (pintype "passive"))
      (node (ref "SG1") (pin "P$1") (pinfunction "1_P$1") (pintype "passive"))
    )
    (net (code "195") (name "unconnected-(IC3-DVDD{slash}DP-Pad19)") (class "Default")
      (node (ref "IC3") (pin "19") (pinfunction "DVDD/DP_19") (pintype "bidirectional"))
    )
    (net (code "196") (name "unconnected-(IC3-P0_0-Pad16)") (class "Default")
      (node (ref "IC3") (pin "16") (pinfunction "P0_0_16") (pintype "bidirectional"))
    )
    (net (code "197") (name "unconnected-(IC3-P0_4{slash}CTS_IN-Pad18)") (class "Default")
      (node (ref "IC3") (pin "18") (pinfunction "P0_4/CTS_IN_18") (pintype "bidirectional"))
    )
    (net (code "198") (name "unconnected-(IC3-P0_5{slash}DM-Pad20)") (class "Default")
      (node (ref "IC3") (pin "20") (pinfunction "P0_5/DM_20") (pintype "bidirectional"))
    )
    (net (code "199") (name "unconnected-(IC3-P0_7{slash}5-Pad21)") (class "Default")
      (node (ref "IC3") (pin "21") (pinfunction "P0_7/5_21") (pintype "bidirectional"))
    )
    (net (code "200") (name "unconnected-(IC3-P1_3-Pad11)") (class "Default")
      (node (ref "IC3") (pin "11") (pinfunction "P1_3_11") (pintype "bidirectional"))
    )
    (net (code "201") (name "unconnected-(IC3-P1_7{slash}MISO-Pad1)") (class "Default")
      (node (ref "IC3") (pin "1") (pinfunction "P1_7/MISO_1") (pintype "bidirectional"))
    )
    (net (code "202") (name "unconnected-(J3-PadRESERVED)") (class "Default")
      (node (ref "J3") (pin "RESERVED") (pinfunction "RESERVED_RESERVED") (pintype "no_connect"))
    )
    (net (code "203") (name "unconnected-(J5-NC-PadP8)") (class "Default")
      (node (ref "J5") (pin "P8") (pinfunction "NC_P8") (pintype "bidirectional"))
    )
    (net (code "204") (name "unconnected-(J5-RSV-PadP1)") (class "Default")
      (node (ref "J5") (pin "P1") (pinfunction "RSV_P1") (pintype "bidirectional"))
    )
    (net (code "205") (name "unconnected-(J6-AUX-Pad4)") (class "Default")
      (node (ref "J6") (pin "4") (pinfunction "AUX_4") (pintype "bidirectional"))
    )
    (net (code "206") (name "unconnected-(J7-NC-Pad1)") (class "Default")
      (node (ref "J7") (pin "1") (pinfunction "NC_1") (pintype "bidirectional"))
    )
    (net (code "207") (name "unconnected-(J7-NC-Pad30)") (class "Default")
      (node (ref "J7") (pin "30") (pinfunction "NC_30") (pintype "bidirectional"))
    )
    (net (code "208") (name "unconnected-(JP2-Pad7)") (class "Default")
      (node (ref "JP2") (pin "7") (pinfunction "7_7") (pintype "passive"))
    )
  )
)
